# power_supply_module.net
KiCad netlist of a schematic drawn in EAGLE
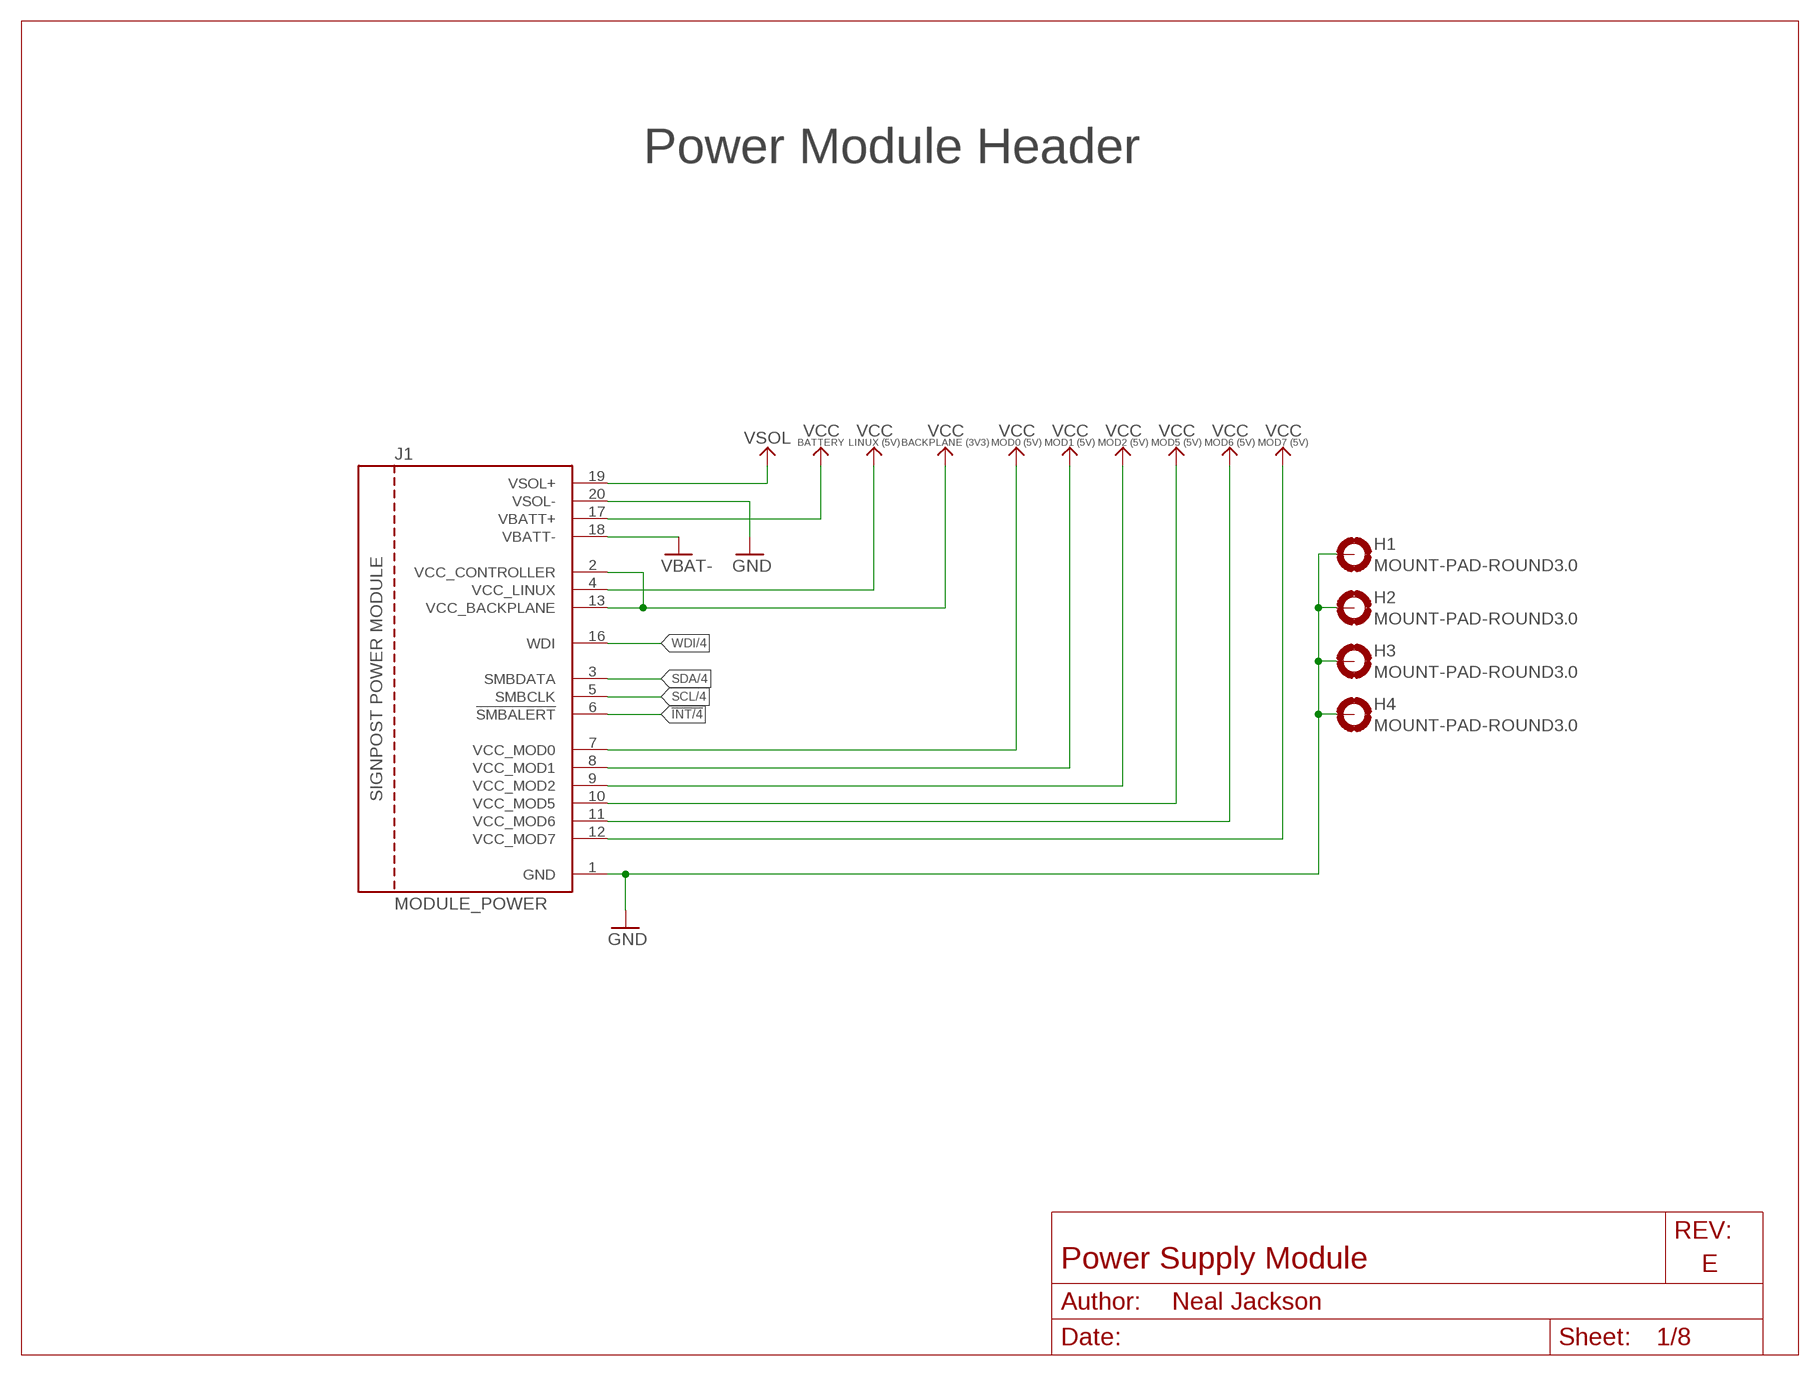
[diagram p0: schematic, sheet 1]
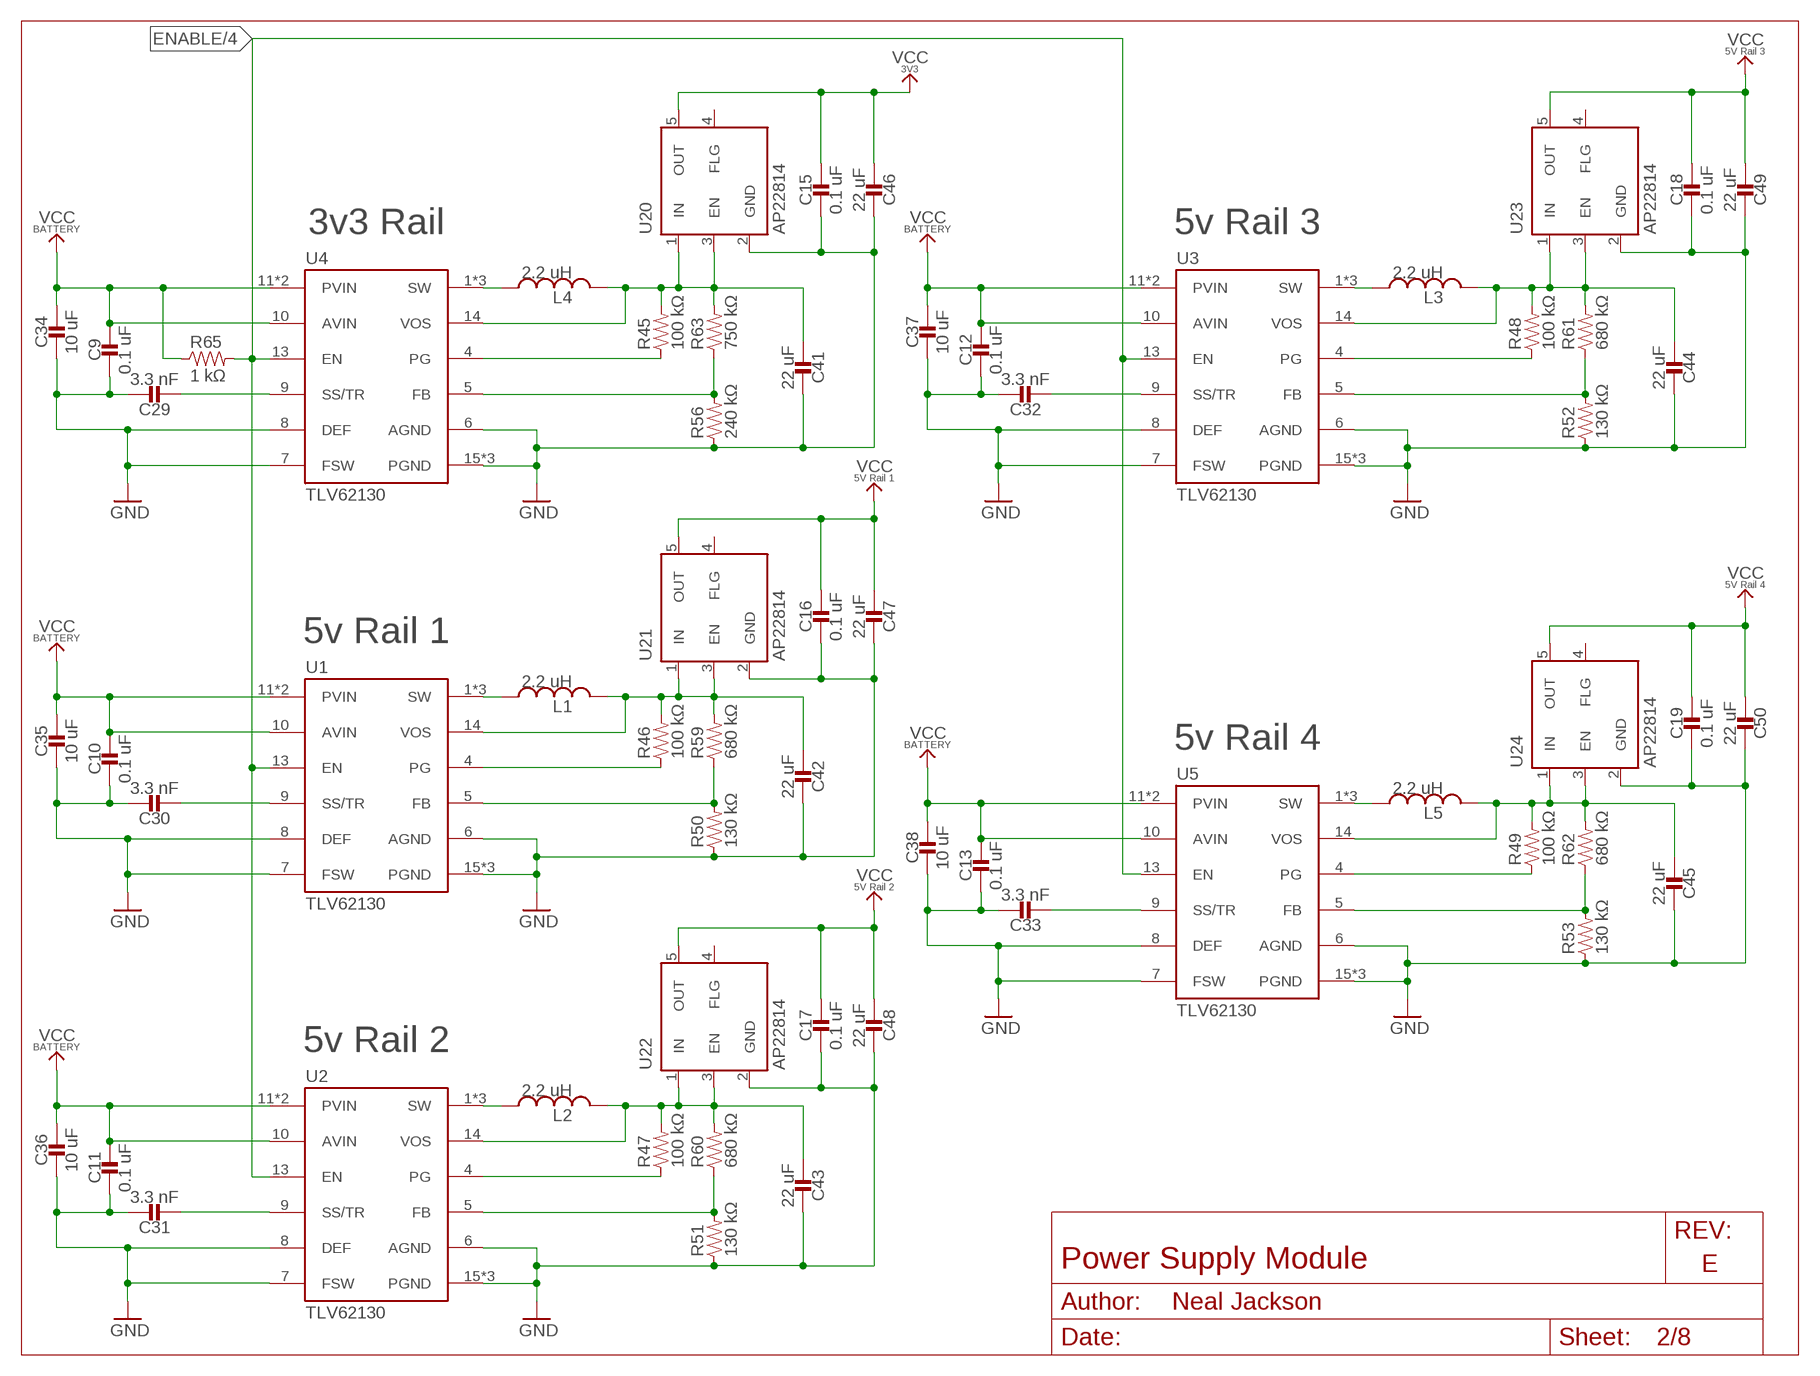
[diagram p1: schematic, sheet 2]
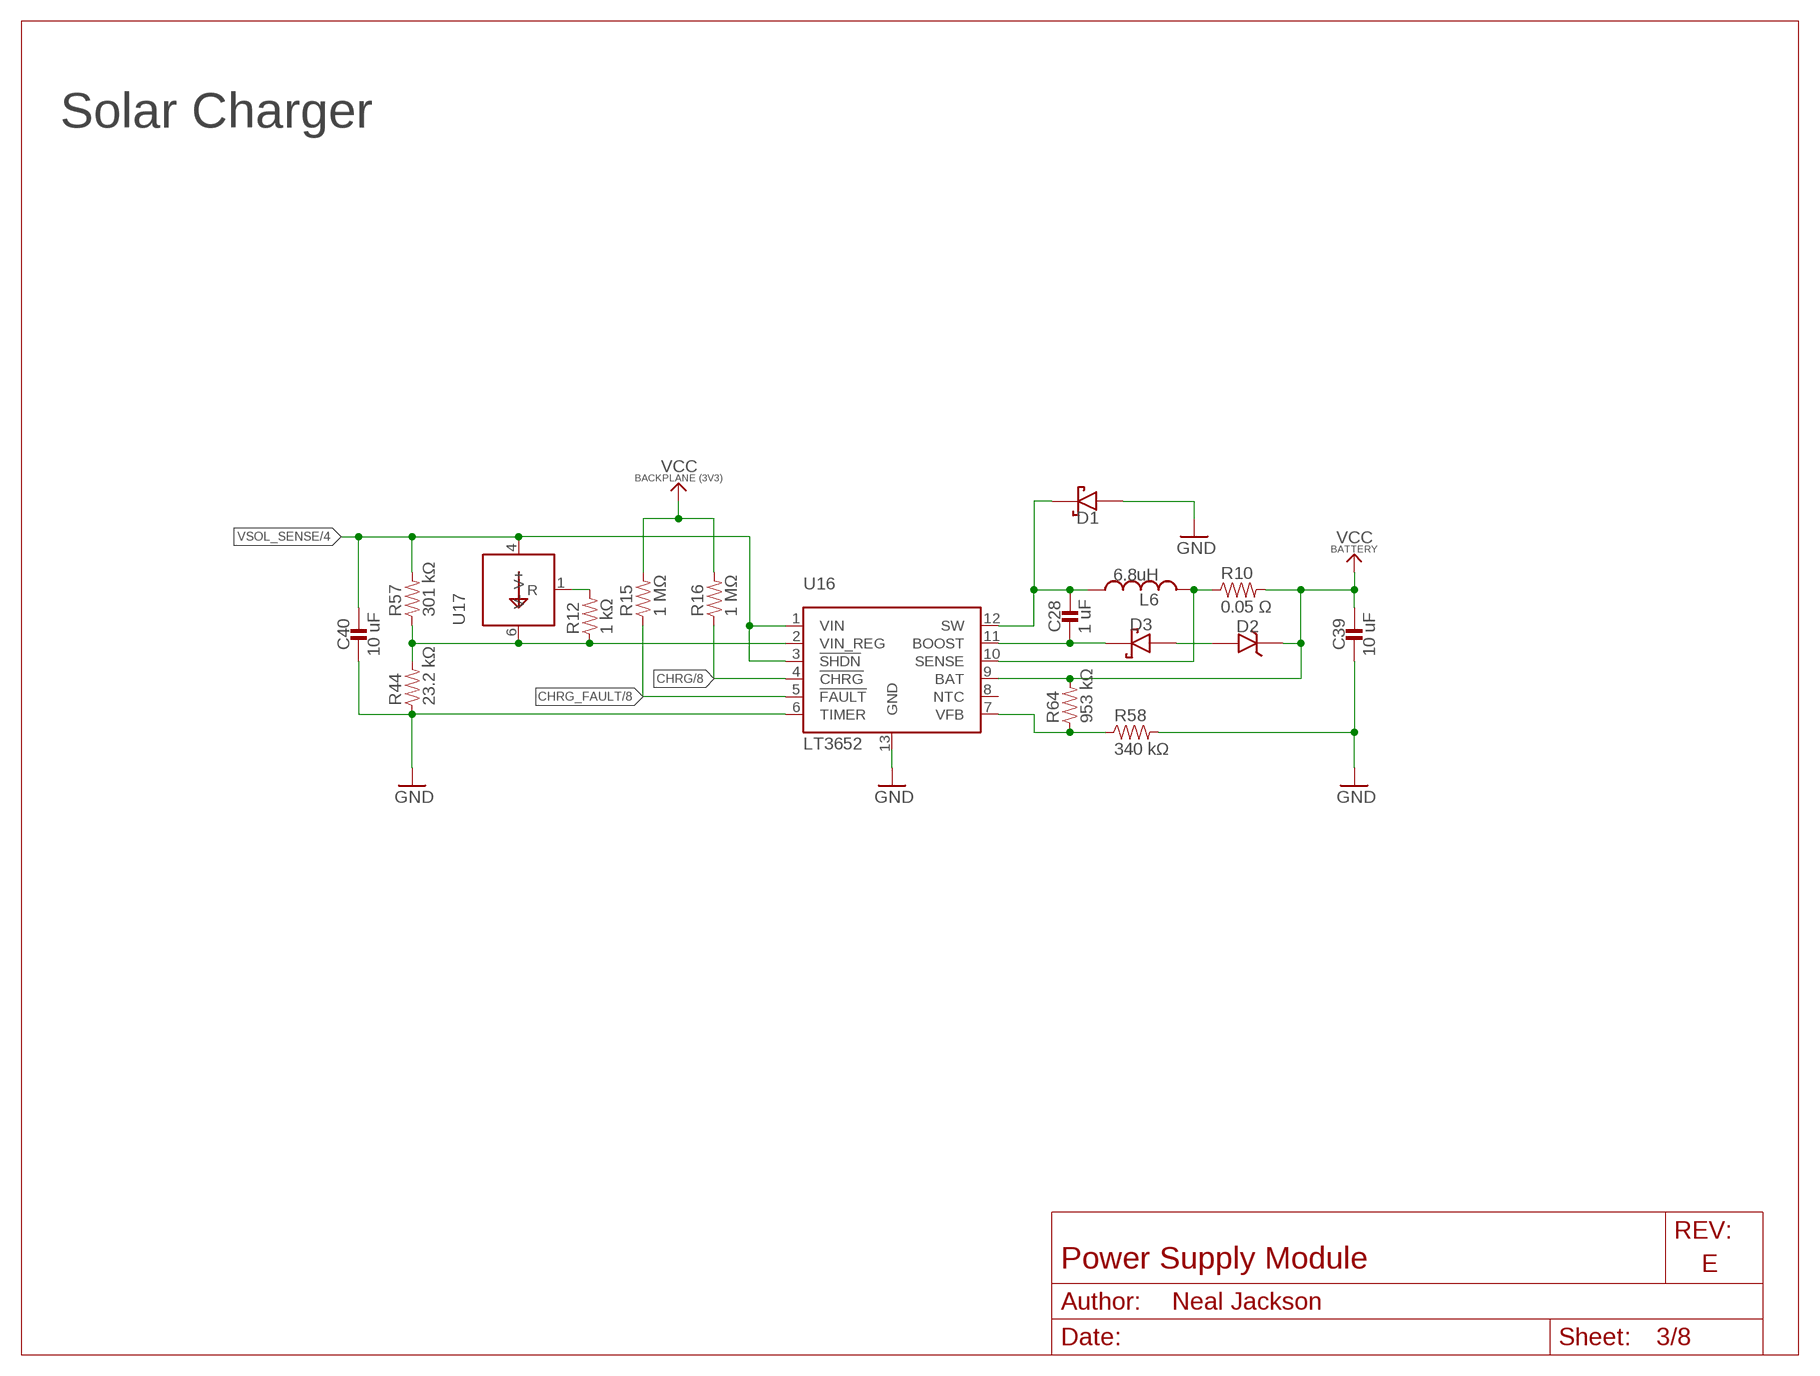
[diagram p2: schematic, sheet 3]
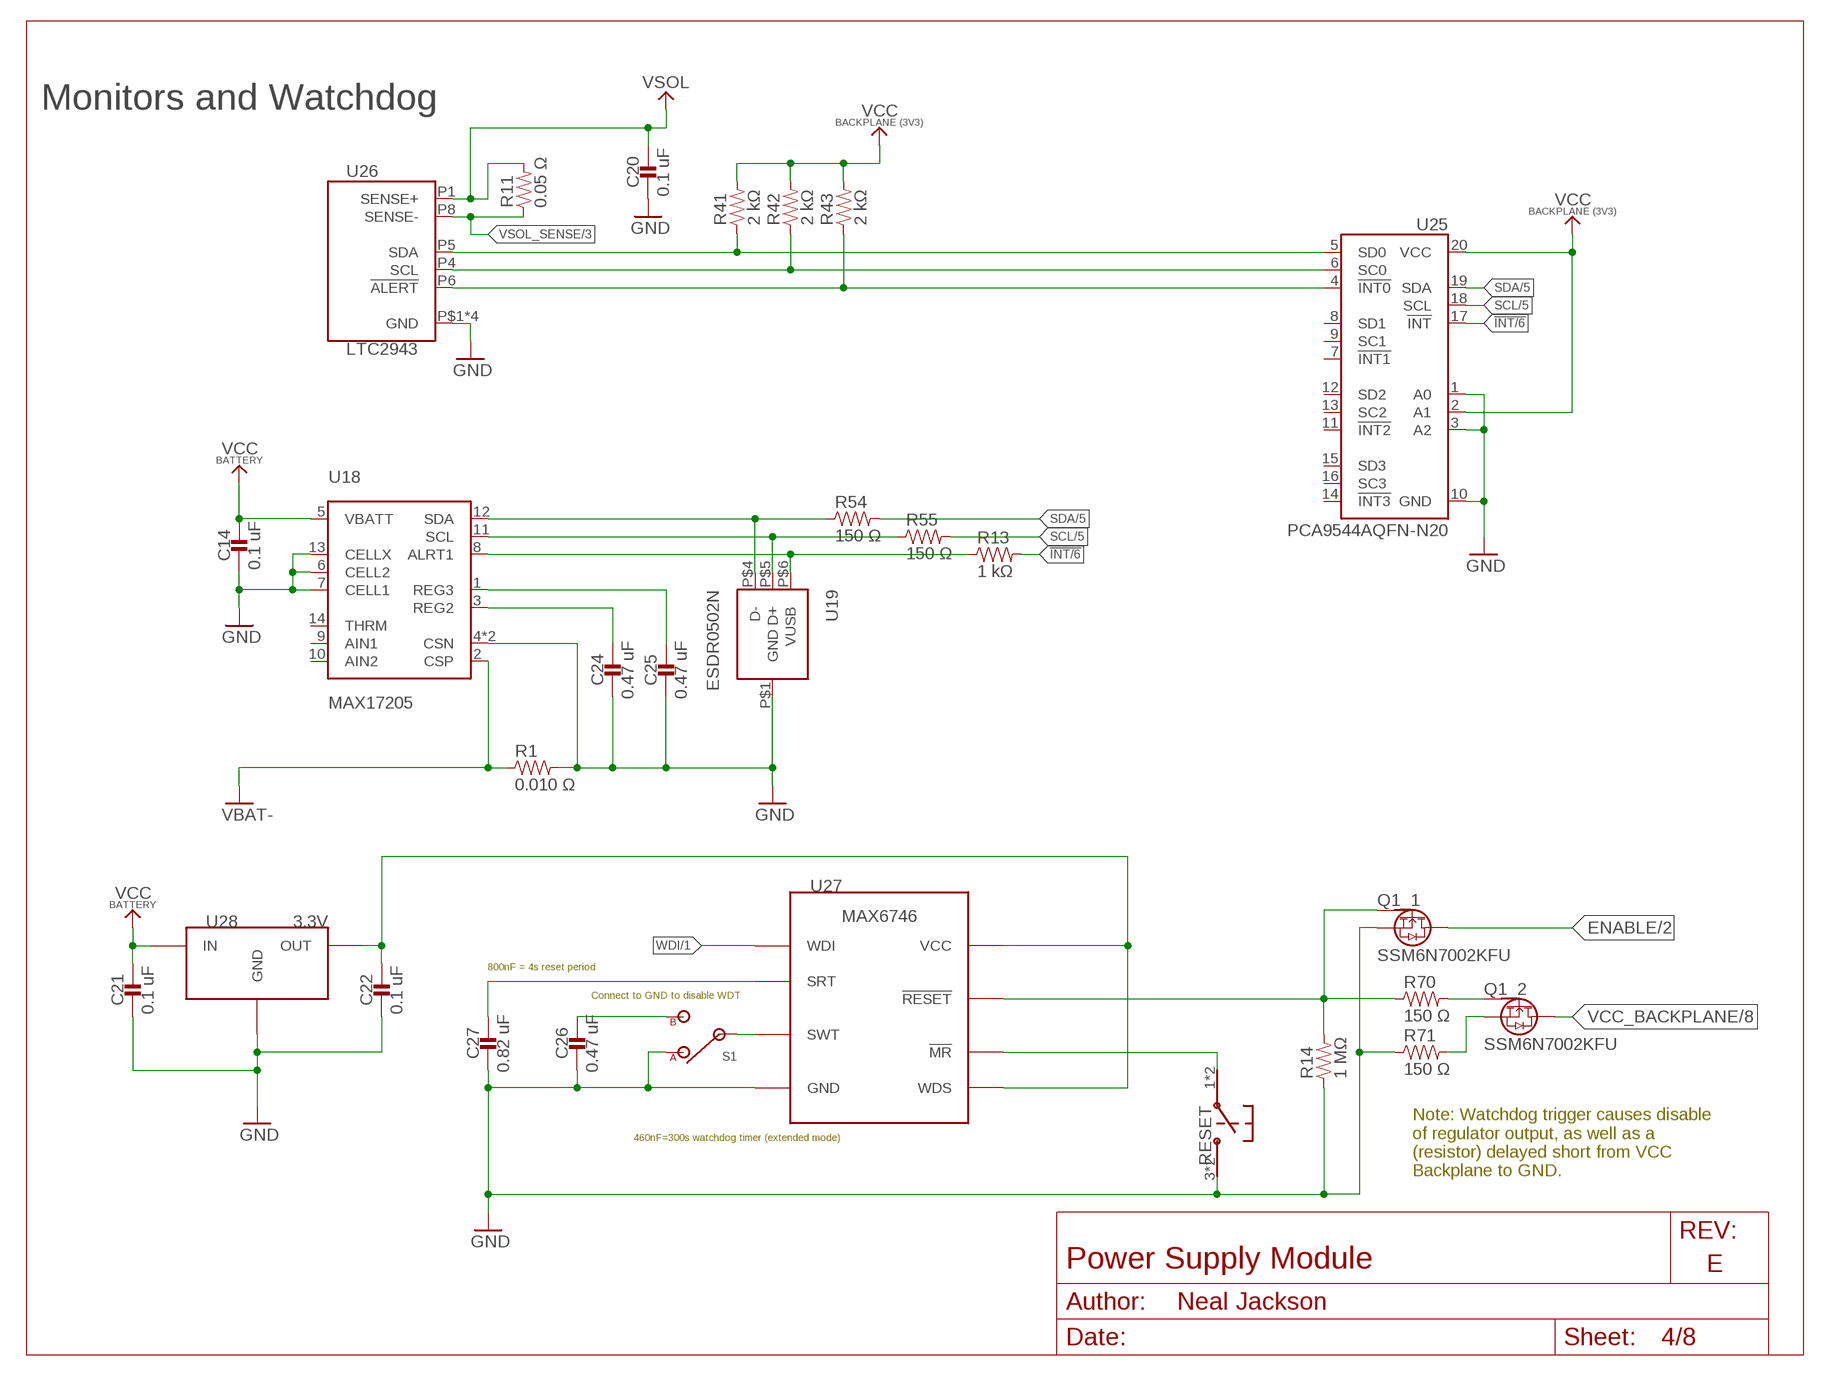
[diagram p3: schematic, sheet 4]
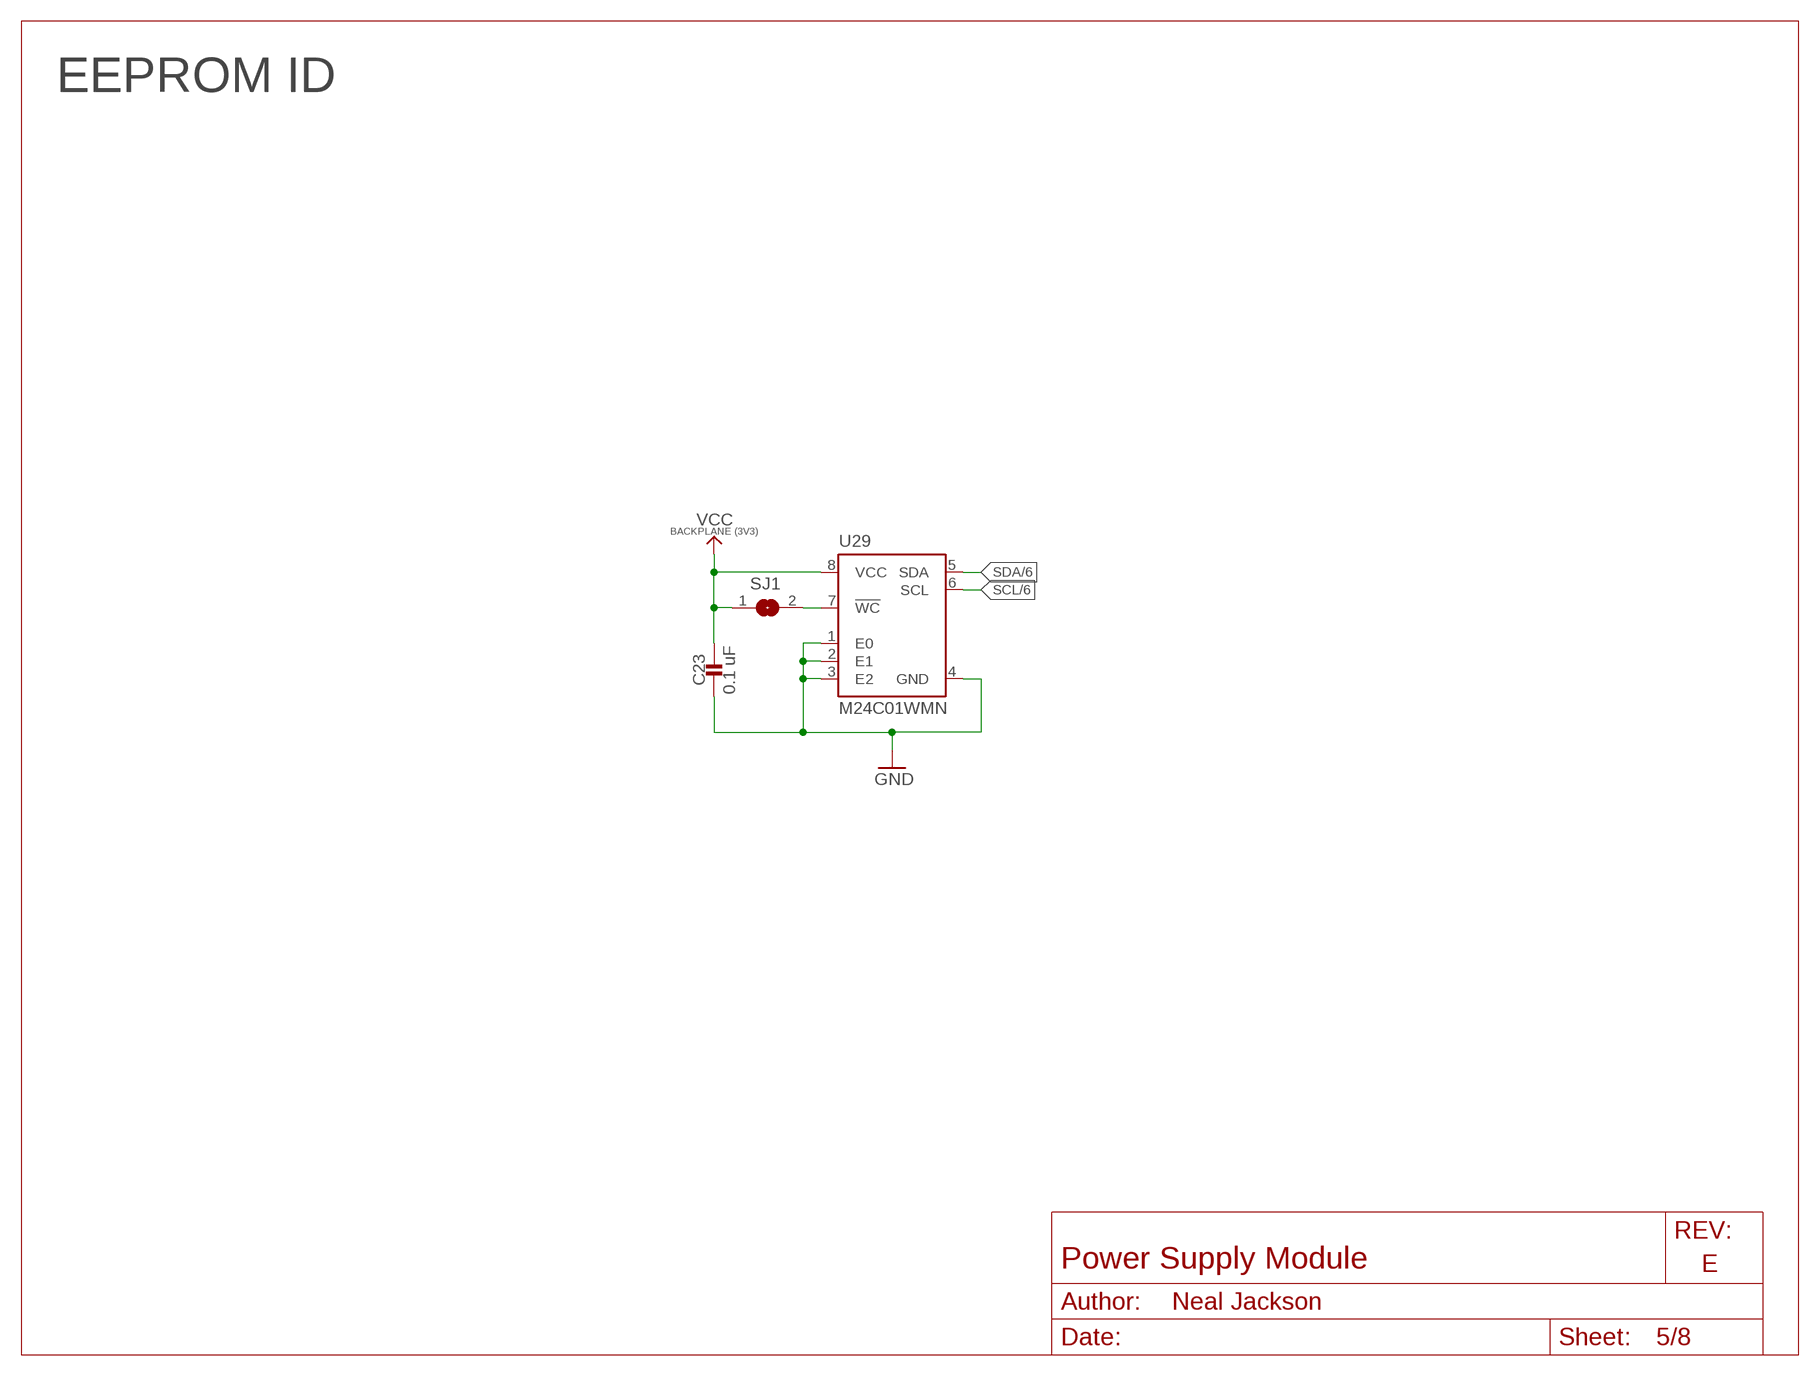
[diagram p4: schematic, sheet 5]
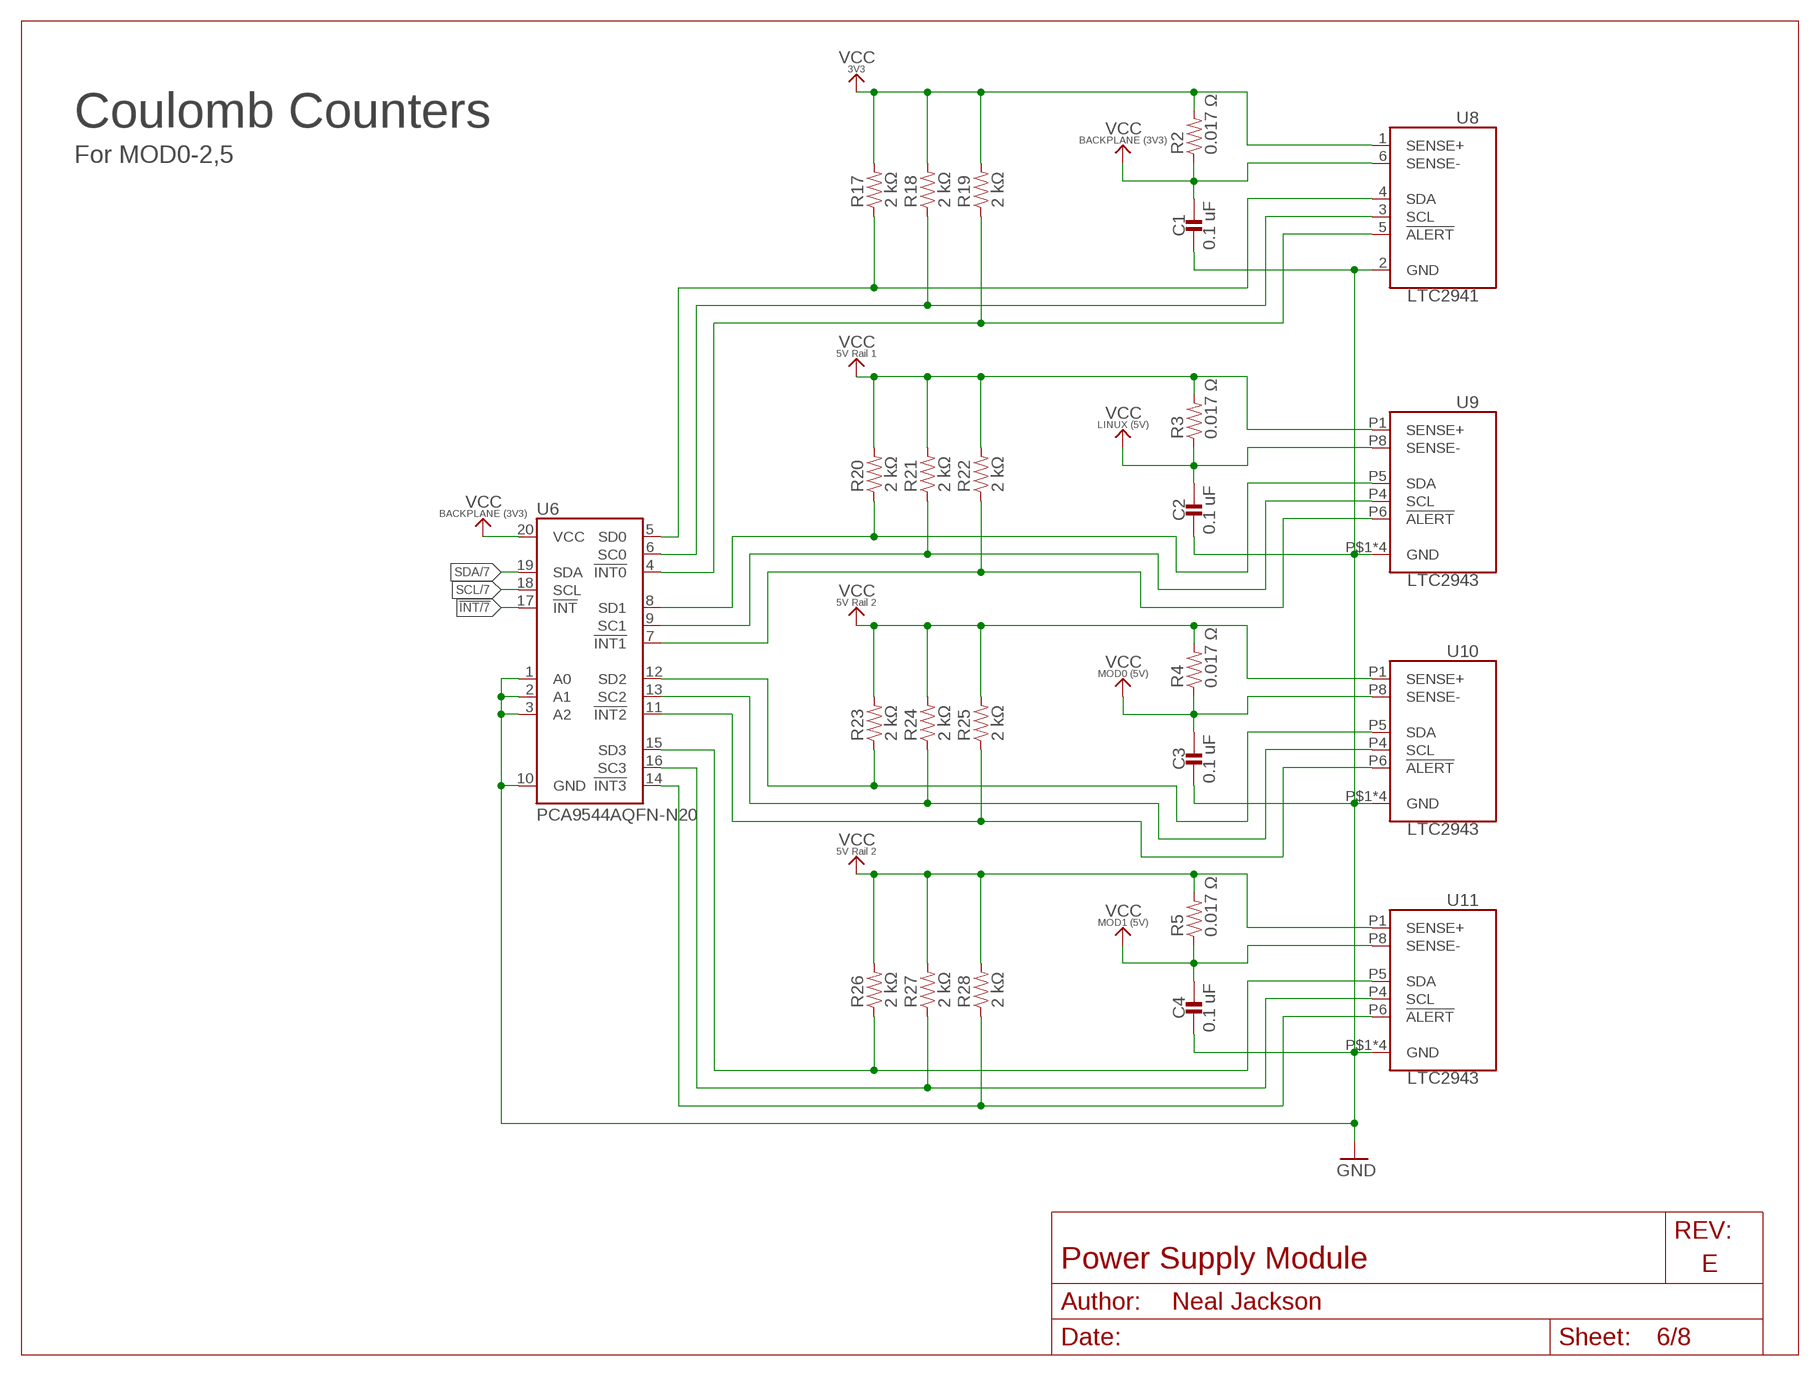
[diagram p5: schematic, sheet 6]
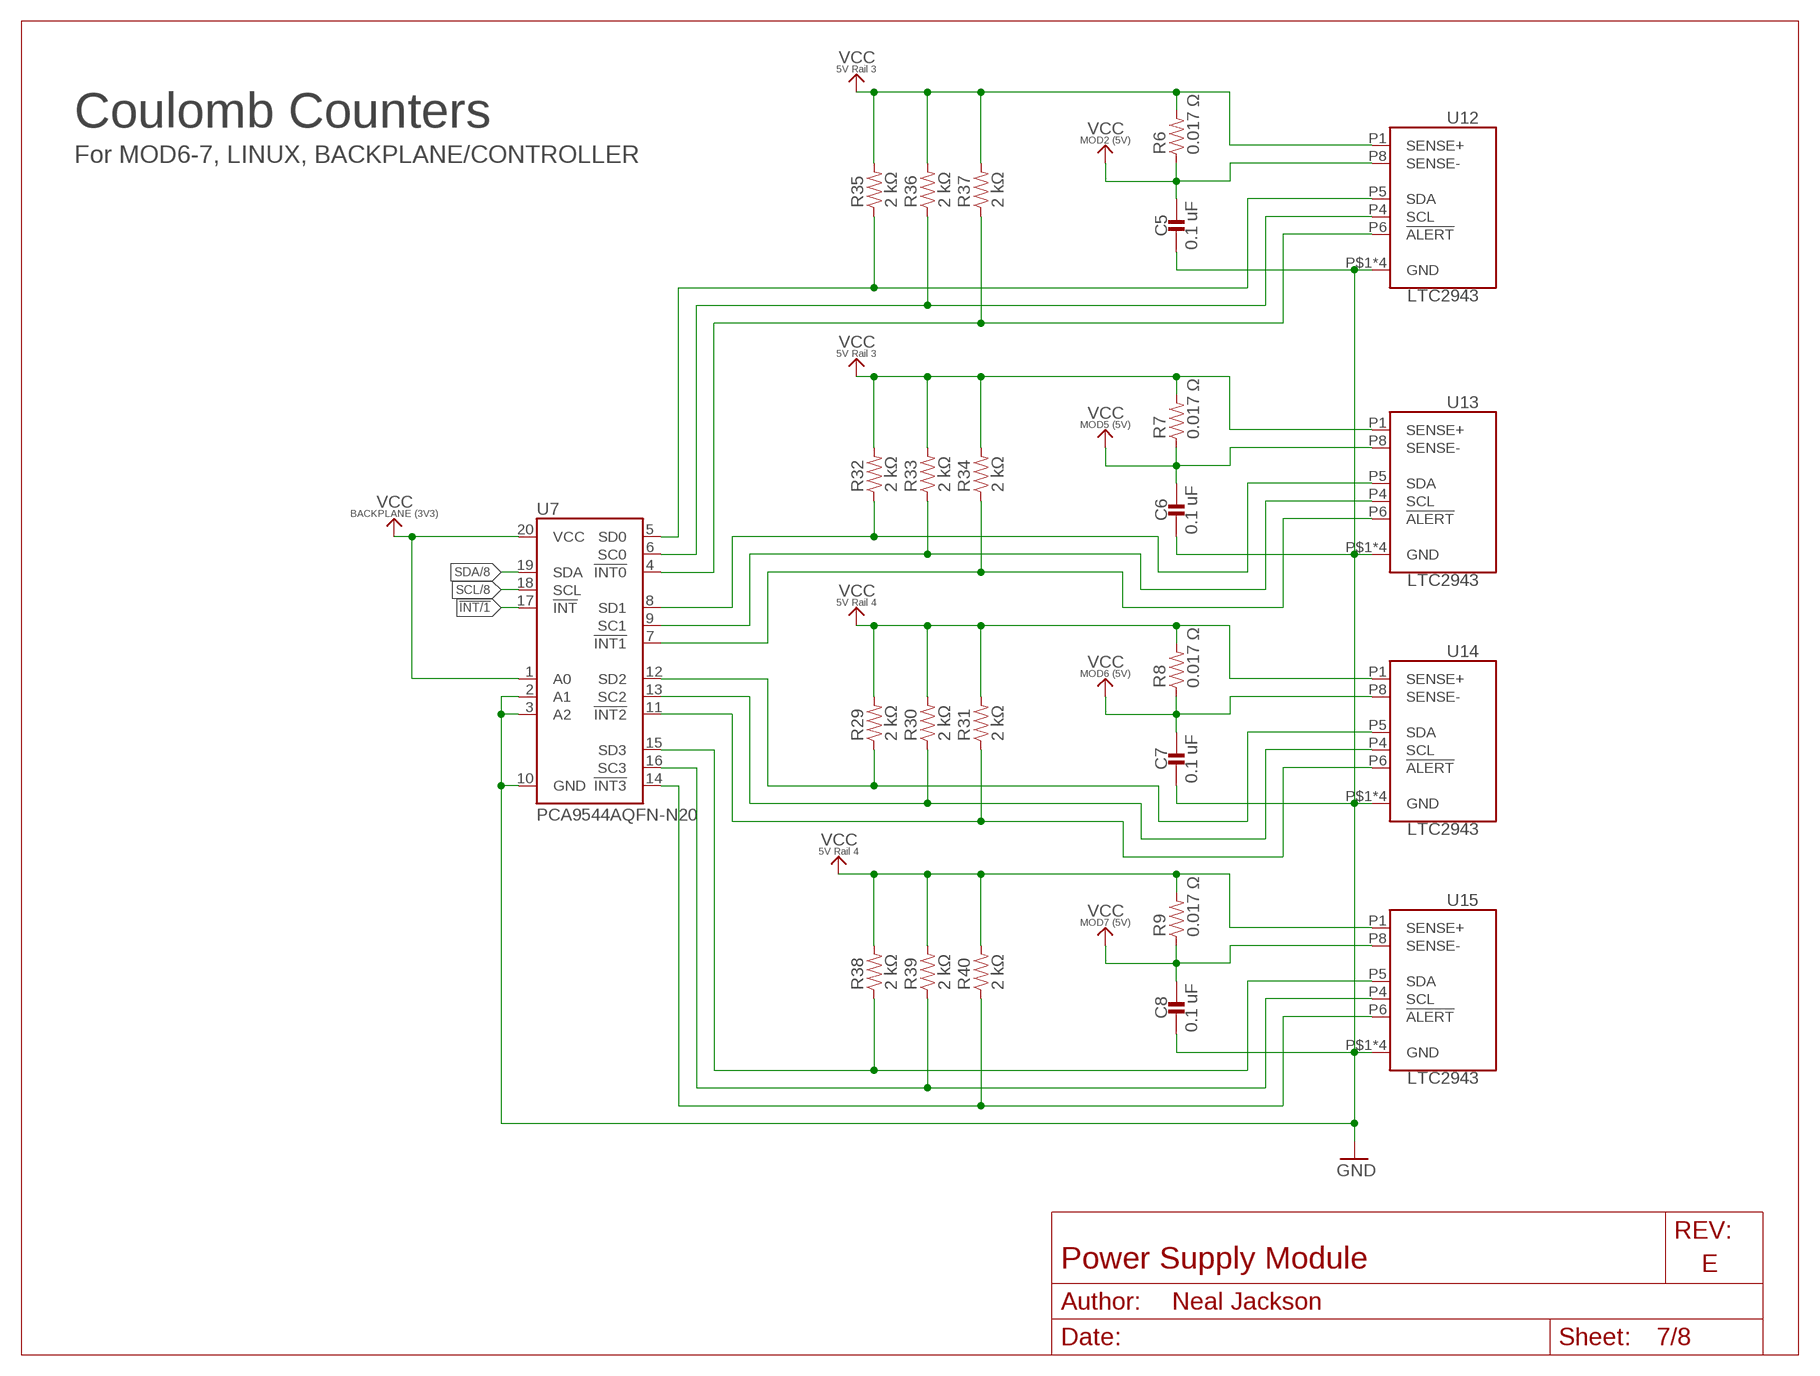
[diagram p6: schematic, sheet 7]
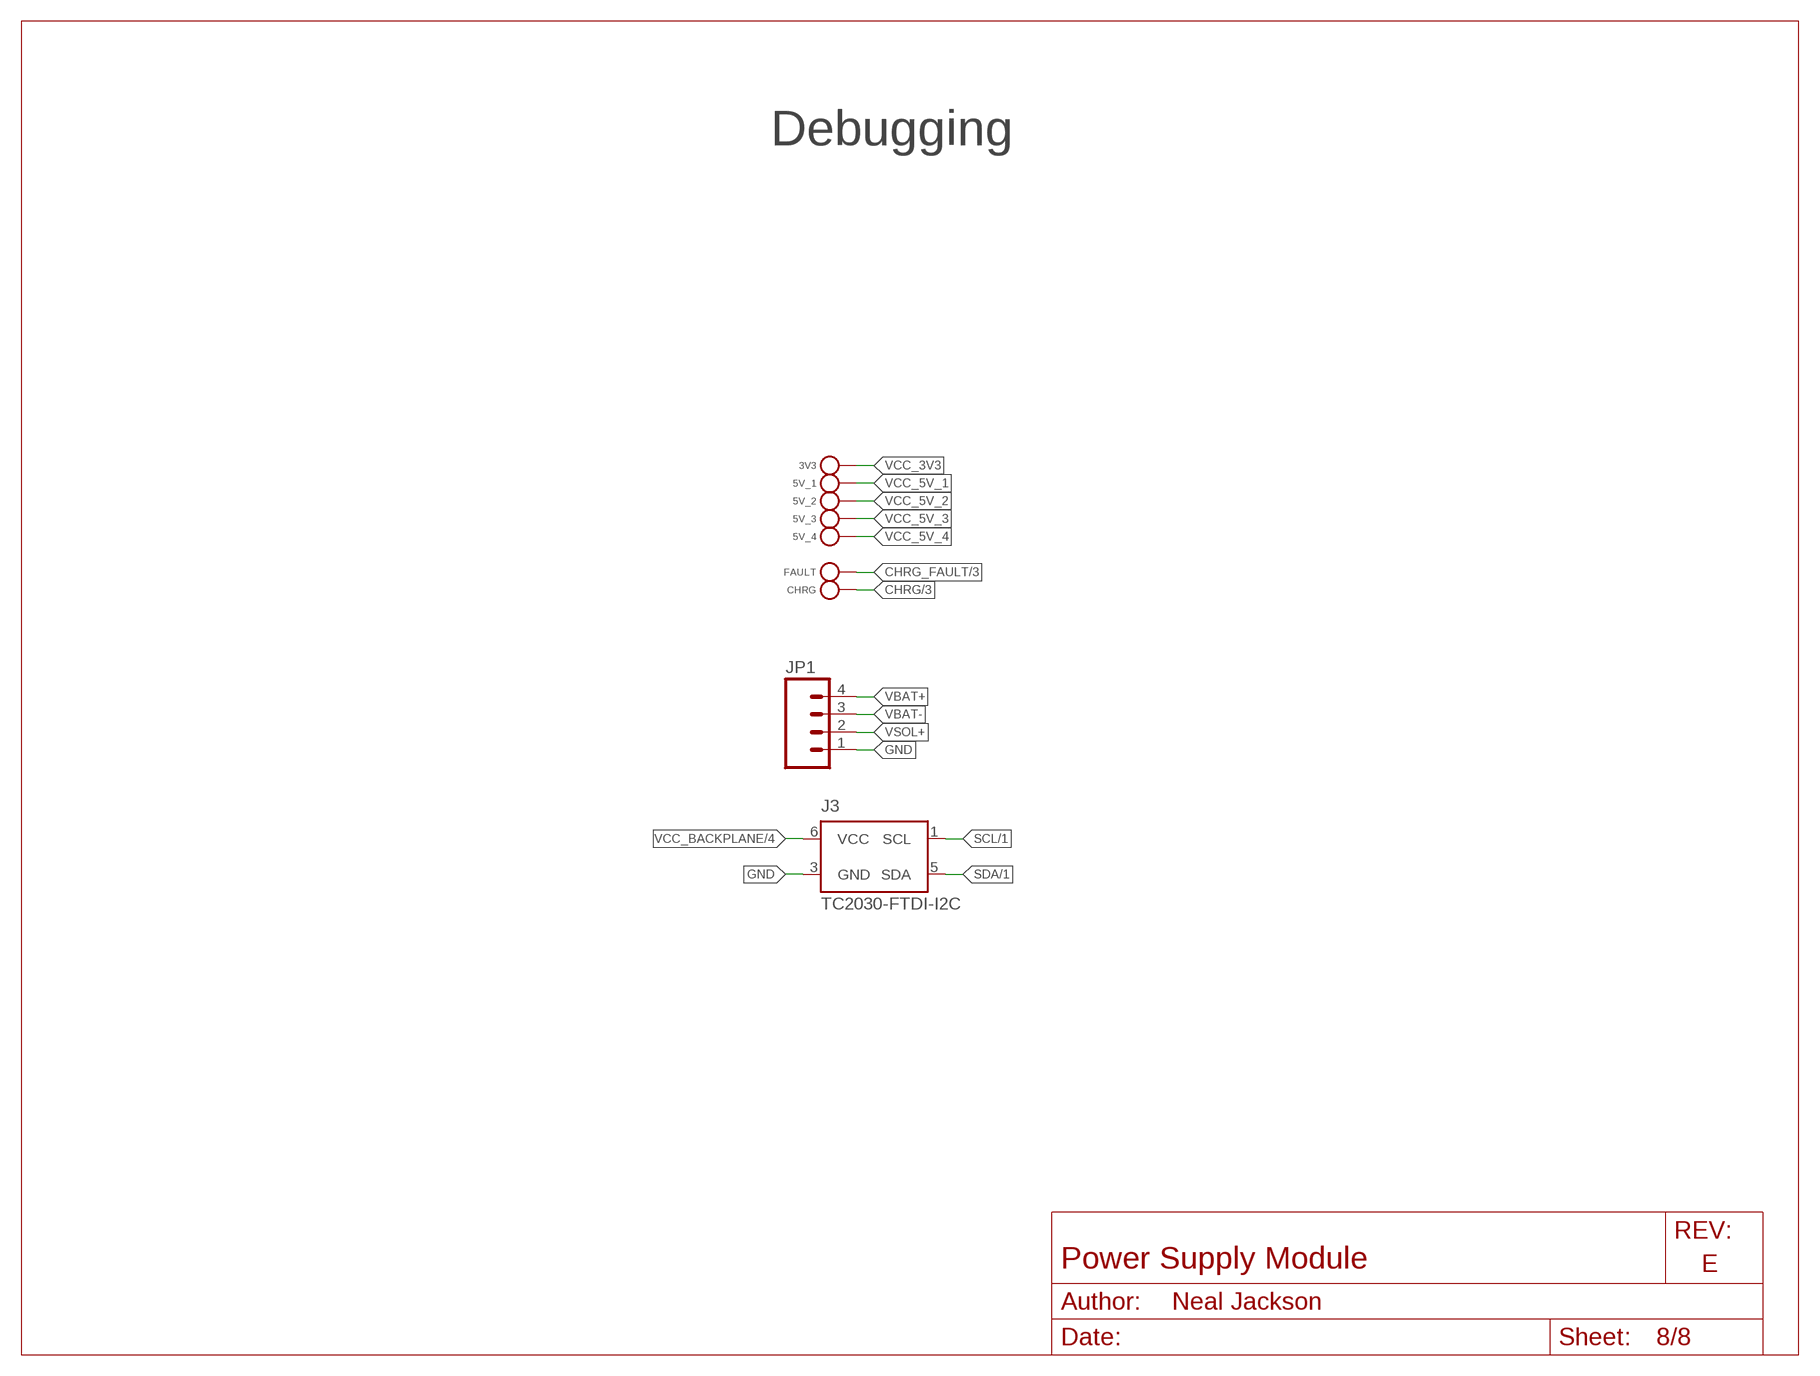
[diagram p7: schematic, sheet 8]

(export (version "E")
  (design (tool "Eeschema 10.0.6"))
  (components
    (comp (ref "C5")
      (value "0.1 uF")
      (footprint "eagle-import:0402_CAP")
      (libsource (lib "eagle-import") (part "CAPACITOR0402_CAP"))
    )
    (comp (ref "C6")
      (value "0.1 uF")
      (footprint "eagle-import:0402_CAP")
      (libsource (lib "eagle-import") (part "CAPACITOR0402_CAP"))
    )
    (comp (ref "C7")
      (value "0.1 uF")
      (footprint "eagle-import:0402_CAP")
      (libsource (lib "eagle-import") (part "CAPACITOR0402_CAP"))
    )
    (comp (ref "C8")
      (value "0.1 uF")
      (footprint "eagle-import:0402_CAP")
      (libsource (lib "eagle-import") (part "CAPACITOR0402_CAP"))
    )
    (comp (ref "R6")
      (value "0.017 Ω")
      (footprint "eagle-import:0805_RES")
      (libsource (lib "eagle-import") (part "RESISTOR0805_RES"))
    )
    (comp (ref "R7")
      (value "0.017 Ω")
      (footprint "eagle-import:0805_RES")
      (libsource (lib "eagle-import") (part "RESISTOR0805_RES"))
    )
    (comp (ref "R8")
      (value "0.017 Ω")
      (footprint "eagle-import:0805_RES")
      (libsource (lib "eagle-import") (part "RESISTOR0805_RES"))
    )
    (comp (ref "R9")
      (value "0.017 Ω")
      (footprint "eagle-import:0805_RES")
      (libsource (lib "eagle-import") (part "RESISTOR0805_RES"))
    )
    (comp (ref "R29")
      (value "2 kΩ")
      (footprint "eagle-import:0402_RES")
      (libsource (lib "eagle-import") (part "RESISTOR0402_RES"))
    )
    (comp (ref "R30")
      (value "2 kΩ")
      (footprint "eagle-import:0402_RES")
      (libsource (lib "eagle-import") (part "RESISTOR0402_RES"))
    )
    (comp (ref "R31")
      (value "2 kΩ")
      (footprint "eagle-import:0402_RES")
      (libsource (lib "eagle-import") (part "RESISTOR0402_RES"))
    )
    (comp (ref "R32")
      (value "2 kΩ")
      (footprint "eagle-import:0402_RES")
      (libsource (lib "eagle-import") (part "RESISTOR0402_RES"))
    )
    (comp (ref "R33")
      (value "2 kΩ")
      (footprint "eagle-import:0402_RES")
      (libsource (lib "eagle-import") (part "RESISTOR0402_RES"))
    )
    (comp (ref "R34")
      (value "2 kΩ")
      (footprint "eagle-import:0402_RES")
      (libsource (lib "eagle-import") (part "RESISTOR0402_RES"))
    )
    (comp (ref "R35")
      (value "2 kΩ")
      (footprint "eagle-import:0402_RES")
      (libsource (lib "eagle-import") (part "RESISTOR0402_RES"))
    )
    (comp (ref "R36")
      (value "2 kΩ")
      (footprint "eagle-import:0402_RES")
      (libsource (lib "eagle-import") (part "RESISTOR0402_RES"))
    )
    (comp (ref "R37")
      (value "2 kΩ")
      (footprint "eagle-import:0402_RES")
      (libsource (lib "eagle-import") (part "RESISTOR0402_RES"))
    )
    (comp (ref "R38")
      (value "2 kΩ")
      (footprint "eagle-import:0402_RES")
      (libsource (lib "eagle-import") (part "RESISTOR0402_RES"))
    )
    (comp (ref "R39")
      (value "2 kΩ")
      (footprint "eagle-import:0402_RES")
      (libsource (lib "eagle-import") (part "RESISTOR0402_RES"))
    )
    (comp (ref "R40")
      (value "2 kΩ")
      (footprint "eagle-import:0402_RES")
      (libsource (lib "eagle-import") (part "RESISTOR0402_RES"))
    )
    (comp (ref "U7")
      (value "PCA9544AQFN-N20")
      (footprint "eagle-import:QFN-N20")
      (libsource (lib "eagle-import") (part "PCA9544AQFN-N20"))
    )
    (comp (ref "U12")
      (value "LTC2943")
      (footprint "eagle-import:DFN-8")
      (libsource (lib "eagle-import") (part "LTC2943"))
    )
    (comp (ref "U13")
      (value "LTC2943")
      (footprint "eagle-import:DFN-8")
      (libsource (lib "eagle-import") (part "LTC2943"))
    )
    (comp (ref "U14")
      (value "LTC2943")
      (footprint "eagle-import:DFN-8")
      (libsource (lib "eagle-import") (part "LTC2943"))
    )
    (comp (ref "U15")
      (value "LTC2943")
      (footprint "eagle-import:DFN-8")
      (libsource (lib "eagle-import") (part "LTC2943"))
    )
    (comp (ref "C1")
      (value "0.1 uF")
      (footprint "eagle-import:0402_CAP")
      (libsource (lib "eagle-import") (part "CAPACITOR0402_CAP"))
    )
    (comp (ref "C2")
      (value "0.1 uF")
      (footprint "eagle-import:0402_CAP")
      (libsource (lib "eagle-import") (part "CAPACITOR0402_CAP"))
    )
    (comp (ref "C3")
      (value "0.1 uF")
      (footprint "eagle-import:0402_CAP")
      (libsource (lib "eagle-import") (part "CAPACITOR0402_CAP"))
    )
    (comp (ref "C4")
      (value "0.1 uF")
      (footprint "eagle-import:0402_CAP")
      (libsource (lib "eagle-import") (part "CAPACITOR0402_CAP"))
    )
    (comp (ref "R2")
      (value "0.017 Ω")
      (footprint "eagle-import:0805_RES")
      (libsource (lib "eagle-import") (part "RESISTOR0805_RES"))
    )
    (comp (ref "R3")
      (value "0.017 Ω")
      (footprint "eagle-import:0805_RES")
      (libsource (lib "eagle-import") (part "RESISTOR0805_RES"))
    )
    (comp (ref "R4")
      (value "0.017 Ω")
      (footprint "eagle-import:0805_RES")
      (libsource (lib "eagle-import") (part "RESISTOR0805_RES"))
    )
    (comp (ref "R5")
      (value "0.017 Ω")
      (footprint "eagle-import:0805_RES")
      (libsource (lib "eagle-import") (part "RESISTOR0805_RES"))
    )
    (comp (ref "R17")
      (value "2 kΩ")
      (footprint "eagle-import:0402_RES")
      (libsource (lib "eagle-import") (part "RESISTOR0402_RES"))
    )
    (comp (ref "R18")
      (value "2 kΩ")
      (footprint "eagle-import:0402_RES")
      (libsource (lib "eagle-import") (part "RESISTOR0402_RES"))
    )
    (comp (ref "R19")
      (value "2 kΩ")
      (footprint "eagle-import:0402_RES")
      (libsource (lib "eagle-import") (part "RESISTOR0402_RES"))
    )
    (comp (ref "R20")
      (value "2 kΩ")
      (footprint "eagle-import:0402_RES")
      (libsource (lib "eagle-import") (part "RESISTOR0402_RES"))
    )
    (comp (ref "R21")
      (value "2 kΩ")
      (footprint "eagle-import:0402_RES")
      (libsource (lib "eagle-import") (part "RESISTOR0402_RES"))
    )
    (comp (ref "R22")
      (value "2 kΩ")
      (footprint "eagle-import:0402_RES")
      (libsource (lib "eagle-import") (part "RESISTOR0402_RES"))
    )
    (comp (ref "R23")
      (value "2 kΩ")
      (footprint "eagle-import:0402_RES")
      (libsource (lib "eagle-import") (part "RESISTOR0402_RES"))
    )
    (comp (ref "R24")
      (value "2 kΩ")
      (footprint "eagle-import:0402_RES")
      (libsource (lib "eagle-import") (part "RESISTOR0402_RES"))
    )
    (comp (ref "R25")
      (value "2 kΩ")
      (footprint "eagle-import:0402_RES")
      (libsource (lib "eagle-import") (part "RESISTOR0402_RES"))
    )
    (comp (ref "R26")
      (value "2 kΩ")
      (footprint "eagle-import:0402_RES")
      (libsource (lib "eagle-import") (part "RESISTOR0402_RES"))
    )
    (comp (ref "R27")
      (value "2 kΩ")
      (footprint "eagle-import:0402_RES")
      (libsource (lib "eagle-import") (part "RESISTOR0402_RES"))
    )
    (comp (ref "R28")
      (value "2 kΩ")
      (footprint "eagle-import:0402_RES")
      (libsource (lib "eagle-import") (part "RESISTOR0402_RES"))
    )
    (comp (ref "U6")
      (value "PCA9544AQFN-N20")
      (footprint "eagle-import:QFN-N20")
      (libsource (lib "eagle-import") (part "PCA9544AQFN-N20"))
    )
    (comp (ref "U8")
      (value "LTC2941")
      (footprint "eagle-import:DFN-6-2MMX3MM")
      (libsource (lib "eagle-import") (part "LTC2941"))
    )
    (comp (ref "U9")
      (value "LTC2943")
      (footprint "eagle-import:DFN-8")
      (libsource (lib "eagle-import") (part "LTC2943"))
    )
    (comp (ref "U10")
      (value "LTC2943")
      (footprint "eagle-import:DFN-8")
      (libsource (lib "eagle-import") (part "LTC2943"))
    )
    (comp (ref "U11")
      (value "LTC2943")
      (footprint "eagle-import:DFN-8")
      (libsource (lib "eagle-import") (part "LTC2943"))
    )
    (comp (ref "C9")
      (value "0.1 uF")
      (footprint "eagle-import:0402_CAP")
      (libsource (lib "eagle-import") (part "CAPACITOR0402_CAP"))
    )
    (comp (ref "C10")
      (value "0.1 uF")
      (footprint "eagle-import:0402_CAP")
      (libsource (lib "eagle-import") (part "CAPACITOR0402_CAP"))
    )
    (comp (ref "C11")
      (value "0.1 uF")
      (footprint "eagle-import:0402_CAP")
      (libsource (lib "eagle-import") (part "CAPACITOR0402_CAP"))
    )
    (comp (ref "C12")
      (value "0.1 uF")
      (footprint "eagle-import:0402_CAP")
      (libsource (lib "eagle-import") (part "CAPACITOR0402_CAP"))
    )
    (comp (ref "C13")
      (value "0.1 uF")
      (footprint "eagle-import:0402_CAP")
      (libsource (lib "eagle-import") (part "CAPACITOR0402_CAP"))
    )
    (comp (ref "C15")
      (value "0.1 uF")
      (footprint "eagle-import:0402_CAP")
      (libsource (lib "eagle-import") (part "CAPACITOR0402_CAP"))
    )
    (comp (ref "C16")
      (value "0.1 uF")
      (footprint "eagle-import:0402_CAP")
      (libsource (lib "eagle-import") (part "CAPACITOR0402_CAP"))
    )
    (comp (ref "C17")
      (value "0.1 uF")
      (footprint "eagle-import:0402_CAP")
      (libsource (lib "eagle-import") (part "CAPACITOR0402_CAP"))
    )
    (comp (ref "C18")
      (value "0.1 uF")
      (footprint "eagle-import:0402_CAP")
      (libsource (lib "eagle-import") (part "CAPACITOR0402_CAP"))
    )
    (comp (ref "C19")
      (value "0.1 uF")
      (footprint "eagle-import:0402_CAP")
      (libsource (lib "eagle-import") (part "CAPACITOR0402_CAP"))
    )
    (comp (ref "C29")
      (value "3.3 nF")
      (footprint "eagle-import:0402_CAP")
      (libsource (lib "eagle-import") (part "CAPACITOR0402_CAP"))
    )
    (comp (ref "C30")
      (value "3.3 nF")
      (footprint "eagle-import:0402_CAP")
      (libsource (lib "eagle-import") (part "CAPACITOR0402_CAP"))
    )
    (comp (ref "C31")
      (value "3.3 nF")
      (footprint "eagle-import:0402_CAP")
      (libsource (lib "eagle-import") (part "CAPACITOR0402_CAP"))
    )
    (comp (ref "C32")
      (value "3.3 nF")
      (footprint "eagle-import:0402_CAP")
      (libsource (lib "eagle-import") (part "CAPACITOR0402_CAP"))
    )
    (comp (ref "C33")
      (value "3.3 nF")
      (footprint "eagle-import:0402_CAP")
      (libsource (lib "eagle-import") (part "CAPACITOR0402_CAP"))
    )
    (comp (ref "C34")
      (value "10 uF")
      (footprint "eagle-import:0805_CAP")
      (libsource (lib "eagle-import") (part "CAPACITOR0805_CAP"))
    )
    (comp (ref "C35")
      (value "10 uF")
      (footprint "eagle-import:0805_CAP")
      (libsource (lib "eagle-import") (part "CAPACITOR0805_CAP"))
    )
    (comp (ref "C36")
      (value "10 uF")
      (footprint "eagle-import:0805_CAP")
      (libsource (lib "eagle-import") (part "CAPACITOR0805_CAP"))
    )
    (comp (ref "C37")
      (value "10 uF")
      (footprint "eagle-import:0805_CAP")
      (libsource (lib "eagle-import") (part "CAPACITOR0805_CAP"))
    )
    (comp (ref "C38")
      (value "10 uF")
      (footprint "eagle-import:0805_CAP")
      (libsource (lib "eagle-import") (part "CAPACITOR0805_CAP"))
    )
    (comp (ref "C41")
      (value "22 uF")
      (footprint "eagle-import:0603_CAP")
      (libsource (lib "eagle-import") (part "CAPACITOR0603_CAP"))
    )
    (comp (ref "C42")
      (value "22 uF")
      (footprint "eagle-import:0603_CAP")
      (libsource (lib "eagle-import") (part "CAPACITOR0603_CAP"))
    )
    (comp (ref "C43")
      (value "22 uF")
      (footprint "eagle-import:0603_CAP")
      (libsource (lib "eagle-import") (part "CAPACITOR0603_CAP"))
    )
    (comp (ref "C44")
      (value "22 uF")
      (footprint "eagle-import:0603_CAP")
      (libsource (lib "eagle-import") (part "CAPACITOR0603_CAP"))
    )
    (comp (ref "C45")
      (value "22 uF")
      (footprint "eagle-import:0603_CAP")
      (libsource (lib "eagle-import") (part "CAPACITOR0603_CAP"))
    )
    (comp (ref "C46")
      (value "22 uF")
      (footprint "eagle-import:0603_CAP")
      (libsource (lib "eagle-import") (part "CAPACITOR0603_CAP"))
    )
    (comp (ref "C47")
      (value "22 uF")
      (footprint "eagle-import:0603_CAP")
      (libsource (lib "eagle-import") (part "CAPACITOR0603_CAP"))
    )
    (comp (ref "C48")
      (value "22 uF")
      (footprint "eagle-import:0603_CAP")
      (libsource (lib "eagle-import") (part "CAPACITOR0603_CAP"))
    )
    (comp (ref "C49")
      (value "22 uF")
      (footprint "eagle-import:0603_CAP")
      (libsource (lib "eagle-import") (part "CAPACITOR0603_CAP"))
    )
    (comp (ref "C50")
      (value "22 uF")
      (footprint "eagle-import:0603_CAP")
      (libsource (lib "eagle-import") (part "CAPACITOR0603_CAP"))
    )
    (comp (ref "L1")
      (value "2.2 uH")
      (footprint "eagle-import:IHL-1212BZ-11")
      (fields (field (name "MF") "Vishay Dale"))
      (libsource (lib "eagle-import") (part "INDUCTORIHL"))
    )
    (comp (ref "L2")
      (value "2.2 uH")
      (footprint "eagle-import:IHL-1212BZ-11")
      (fields (field (name "MF") "Vishay Dale"))
      (libsource (lib "eagle-import") (part "INDUCTORIHL"))
    )
    (comp (ref "L3")
      (value "2.2 uH")
      (footprint "eagle-import:IHL-1212BZ-11")
      (fields (field (name "MF") "Vishay Dale"))
      (libsource (lib "eagle-import") (part "INDUCTORIHL"))
    )
    (comp (ref "L4")
      (value "2.2 uH")
      (footprint "eagle-import:IHL-1212BZ-11")
      (fields (field (name "MF") "Vishay Dale"))
      (libsource (lib "eagle-import") (part "INDUCTORIHL"))
    )
    (comp (ref "L5")
      (value "2.2 uH")
      (footprint "eagle-import:IHL-1212BZ-11")
      (fields (field (name "MF") "Vishay Dale"))
      (libsource (lib "eagle-import") (part "INDUCTORIHL"))
    )
    (comp (ref "R45")
      (value "100 kΩ")
      (footprint "eagle-import:0402_RES")
      (libsource (lib "eagle-import") (part "RESISTOR0402_RES"))
    )
    (comp (ref "R46")
      (value "100 kΩ")
      (footprint "eagle-import:0402_RES")
      (libsource (lib "eagle-import") (part "RESISTOR0402_RES"))
    )
    (comp (ref "R47")
      (value "100 kΩ")
      (footprint "eagle-import:0402_RES")
      (libsource (lib "eagle-import") (part "RESISTOR0402_RES"))
    )
    (comp (ref "R48")
      (value "100 kΩ")
      (footprint "eagle-import:0402_RES")
      (libsource (lib "eagle-import") (part "RESISTOR0402_RES"))
    )
    (comp (ref "R49")
      (value "100 kΩ")
      (footprint "eagle-import:0402_RES")
      (libsource (lib "eagle-import") (part "RESISTOR0402_RES"))
    )
    (comp (ref "R50")
      (value "130 kΩ")
      (footprint "eagle-import:0402_RES")
      (libsource (lib "eagle-import") (part "RESISTOR0402_RES"))
    )
    (comp (ref "R51")
      (value "130 kΩ")
      (footprint "eagle-import:0402_RES")
      (libsource (lib "eagle-import") (part "RESISTOR0402_RES"))
    )
    (comp (ref "R52")
      (value "130 kΩ")
      (footprint "eagle-import:0402_RES")
      (libsource (lib "eagle-import") (part "RESISTOR0402_RES"))
    )
    (comp (ref "R53")
      (value "130 kΩ")
      (footprint "eagle-import:0402_RES")
      (libsource (lib "eagle-import") (part "RESISTOR0402_RES"))
    )
    (comp (ref "R56")
      (value "240 kΩ")
      (footprint "eagle-import:0402_RES")
      (libsource (lib "eagle-import") (part "RESISTOR0402_RES"))
    )
    (comp (ref "R59")
      (value "680 kΩ")
      (footprint "eagle-import:0402_RES")
      (libsource (lib "eagle-import") (part "RESISTOR0402_RES"))
    )
    (comp (ref "R60")
      (value "680 kΩ")
      (footprint "eagle-import:0402_RES")
      (libsource (lib "eagle-import") (part "RESISTOR0402_RES"))
    )
    (comp (ref "R61")
      (value "680 kΩ")
      (footprint "eagle-import:0402_RES")
      (libsource (lib "eagle-import") (part "RESISTOR0402_RES"))
    )
    (comp (ref "R62")
      (value "680 kΩ")
      (footprint "eagle-import:0402_RES")
      (libsource (lib "eagle-import") (part "RESISTOR0402_RES"))
    )
    (comp (ref "R63")
      (value "750 kΩ")
      (footprint "eagle-import:0402_RES")
      (libsource (lib "eagle-import") (part "RESISTOR0402_RES"))
    )
    (comp (ref "R65")
      (value "1 kΩ")
      (footprint "eagle-import:0402_RES")
      (libsource (lib "eagle-import") (part "RESISTOR0402_RES"))
    )
    (comp (ref "U1")
      (value "TLV62130")
      (footprint "eagle-import:TQFN-16_3MM")
      (fields (field (name "MF") "Texas Instruments"))
      (libsource (lib "eagle-import") (part "TLV62130"))
    )
    (comp (ref "U2")
      (value "TLV62130")
      (footprint "eagle-import:TQFN-16_3MM")
      (fields (field (name "MF") "Texas Instruments"))
      (libsource (lib "eagle-import") (part "TLV62130"))
    )
    (comp (ref "U3")
      (value "TLV62130")
      (footprint "eagle-import:TQFN-16_3MM")
      (fields (field (name "MF") "Texas Instruments"))
      (libsource (lib "eagle-import") (part "TLV62130"))
    )
    (comp (ref "U4")
      (value "TLV62130")
      (footprint "eagle-import:TQFN-16_3MM")
      (fields (field (name "MF") "Texas Instruments"))
      (libsource (lib "eagle-import") (part "TLV62130"))
    )
    (comp (ref "U5")
      (value "TLV62130")
      (footprint "eagle-import:TQFN-16_3MM")
      (fields (field (name "MF") "Texas Instruments"))
      (libsource (lib "eagle-import") (part "TLV62130"))
    )
    (comp (ref "U20")
      (value "AP22814")
      (footprint "eagle-import:U-DFN2020-6")
      (libsource (lib "eagle-import") (part "AP22814"))
    )
    (comp (ref "U21")
      (value "AP22814")
      (footprint "eagle-import:U-DFN2020-6")
      (libsource (lib "eagle-import") (part "AP22814"))
    )
    (comp (ref "U22")
      (value "AP22814")
      (footprint "eagle-import:U-DFN2020-6")
      (libsource (lib "eagle-import") (part "AP22814"))
    )
    (comp (ref "U23")
      (value "AP22814")
      (footprint "eagle-import:U-DFN2020-6")
      (libsource (lib "eagle-import") (part "AP22814"))
    )
    (comp (ref "U24")
      (value "AP22814")
      (footprint "eagle-import:U-DFN2020-6")
      (libsource (lib "eagle-import") (part "AP22814"))
    )
    (comp (ref "3V3")
      (value "TEST_POINT_0.040IN")
      (footprint "eagle-import:TESTPOINT_0.040IN")
      (libsource (lib "eagle-import") (part "TEST_POINT_0.040IN"))
    )
    (comp (ref "5V_1")
      (value "TEST_POINT_0.040IN")
      (footprint "eagle-import:TESTPOINT_0.040IN")
      (libsource (lib "eagle-import") (part "TEST_POINT_0.040IN"))
    )
    (comp (ref "5V_2")
      (value "TEST_POINT_0.040IN")
      (footprint "eagle-import:TESTPOINT_0.040IN")
      (libsource (lib "eagle-import") (part "TEST_POINT_0.040IN"))
    )
    (comp (ref "5V_3")
      (value "TEST_POINT_0.040IN")
      (footprint "eagle-import:TESTPOINT_0.040IN")
      (libsource (lib "eagle-import") (part "TEST_POINT_0.040IN"))
    )
    (comp (ref "5V_4")
      (value "TEST_POINT_0.040IN")
      (footprint "eagle-import:TESTPOINT_0.040IN")
      (libsource (lib "eagle-import") (part "TEST_POINT_0.040IN"))
    )
    (comp (ref "CHRG")
      (value "TEST_POINT_0.040IN")
      (footprint "eagle-import:TESTPOINT_0.040IN")
      (libsource (lib "eagle-import") (part "TEST_POINT_0.040IN"))
    )
    (comp (ref "FAULT")
      (value "TEST_POINT_0.040IN")
      (footprint "eagle-import:TESTPOINT_0.040IN")
      (libsource (lib "eagle-import") (part "TEST_POINT_0.040IN"))
    )
    (comp (ref "J3")
      (value "TC2030-FTDI-I2C")
      (footprint "eagle-import:TC2030-IDC-NL")
      (libsource (lib "eagle-import") (part "TC2030-FTDI-I2C"))
    )
    (comp (ref "JP1")
      (value "M04PTH")
      (footprint "eagle-import:1X04")
      (libsource (lib "eagle-import") (part "M04PTH"))
    )
    (comp (ref "H1")
      (value "MOUNT-PAD-ROUND3.0")
      (footprint "eagle-import:3,0-PAD")
      (libsource (lib "eagle-import") (part "MOUNT-PAD-ROUND3.0"))
    )
    (comp (ref "H2")
      (value "MOUNT-PAD-ROUND3.0")
      (footprint "eagle-import:3,0-PAD")
      (libsource (lib "eagle-import") (part "MOUNT-PAD-ROUND3.0"))
    )
    (comp (ref "H3")
      (value "MOUNT-PAD-ROUND3.0")
      (footprint "eagle-import:3,0-PAD")
      (libsource (lib "eagle-import") (part "MOUNT-PAD-ROUND3.0"))
    )
    (comp (ref "H4")
      (value "MOUNT-PAD-ROUND3.0")
      (footprint "eagle-import:3,0-PAD")
      (libsource (lib "eagle-import") (part "MOUNT-PAD-ROUND3.0"))
    )
    (comp (ref "J1")
      (value "MODULE_POWER")
      (footprint "eagle-import:MODULE_POWER")
      (libsource (lib "eagle-import") (part "MODULE_POWER"))
    )
    (comp (ref "C28")
      (value "1 uF")
      (footprint "eagle-import:0603_CAP")
      (libsource (lib "eagle-import") (part "CAPACITOR0603_CAP"))
    )
    (comp (ref "C39")
      (value "10 uF")
      (footprint "eagle-import:0805_CAP")
      (libsource (lib "eagle-import") (part "CAPACITOR0805_CAP"))
    )
    (comp (ref "C40")
      (value "10 uF")
      (footprint "eagle-import:0805_CAP")
      (libsource (lib "eagle-import") (part "CAPACITOR0805_CAP"))
    )
    (comp (ref "D1")
      (value "DIODE_SCHOTTKYSOT-23F")
      (footprint "eagle-import:SOT-23F")
      (libsource (lib "eagle-import") (part "DIODE_SCHOTTKYSOT-23F"))
    )
    (comp (ref "D2")
      (value "DIODE_ZENERSOT323")
      (footprint "eagle-import:SOD323")
      (libsource (lib "eagle-import") (part "DIODE_ZENERSOT323"))
    )
    (comp (ref "D3")
      (value "DIODE_SCHOTTKYSOD323")
      (footprint "eagle-import:SOD323")
      (libsource (lib "eagle-import") (part "DIODE_SCHOTTKYSOD323"))
    )
    (comp (ref "L6")
      (value "6.8uH")
      (footprint "eagle-import:IHL-2525CZ")
      (libsource (lib "eagle-import") (part "INDUCTORIHL2525CZ"))
    )
    (comp (ref "R10")
      (value "0.05 Ω")
      (footprint "eagle-import:0805_RES")
      (libsource (lib "eagle-import") (part "RESISTOR0805_RES"))
    )
    (comp (ref "R12")
      (value "1 kΩ")
      (footprint "eagle-import:0402_RES")
      (libsource (lib "eagle-import") (part "RESISTOR0402_RES"))
    )
    (comp (ref "R15")
      (value "1 MΩ")
      (footprint "eagle-import:0402_RES")
      (libsource (lib "eagle-import") (part "RESISTOR0402_RES"))
    )
    (comp (ref "R16")
      (value "1 MΩ")
      (footprint "eagle-import:0402_RES")
      (libsource (lib "eagle-import") (part "RESISTOR0402_RES"))
    )
    (comp (ref "R44")
      (value "23.2 kΩ")
      (footprint "eagle-import:0805_RES")
      (libsource (lib "eagle-import") (part "RESISTOR0805_RES"))
    )
    (comp (ref "R57")
      (value "301 kΩ")
      (footprint "eagle-import:0805_RES")
      (libsource (lib "eagle-import") (part "RESISTOR0805_RES"))
    )
    (comp (ref "R58")
      (value "340 kΩ")
      (footprint "eagle-import:0805_RES")
      (libsource (lib "eagle-import") (part "RESISTOR0805_RES"))
    )
    (comp (ref "R64")
      (value "953 kΩ")
      (footprint "eagle-import:0805_RES")
      (libsource (lib "eagle-import") (part "RESISTOR0805_RES"))
    )
    (comp (ref "U16")
      (value "LT3652")
      (footprint "eagle-import:DFN-12_3MM")
      (libsource (lib "eagle-import") (part "LT3652"))
    )
    (comp (ref "U17")
      (value "LM234")
      (footprint "eagle-import:SOIC-8")
      (libsource (lib "eagle-import") (part "LM234"))
    )
    (comp (ref "C14")
      (value "0.1 uF")
      (footprint "eagle-import:0402_CAP")
      (libsource (lib "eagle-import") (part "CAPACITOR0402_CAP"))
    )
    (comp (ref "C20")
      (value "0.1 uF")
      (footprint "eagle-import:0402_CAP")
      (libsource (lib "eagle-import") (part "CAPACITOR0402_CAP"))
    )
    (comp (ref "C21")
      (value "0.1 uF")
      (footprint "eagle-import:0402_CAP")
      (libsource (lib "eagle-import") (part "CAPACITOR0402_CAP"))
    )
    (comp (ref "C22")
      (value "0.1 uF")
      (footprint "eagle-import:0402_CAP")
      (libsource (lib "eagle-import") (part "CAPACITOR0402_CAP"))
    )
    (comp (ref "C24")
      (value "0.47 uF")
      (footprint "eagle-import:0402_CAP")
      (libsource (lib "eagle-import") (part "CAPACITOR0402_CAP"))
    )
    (comp (ref "C25")
      (value "0.47 uF")
      (footprint "eagle-import:0402_CAP")
      (libsource (lib "eagle-import") (part "CAPACITOR0402_CAP"))
    )
    (comp (ref "C26")
      (value "0.47 uF")
      (footprint "eagle-import:0402_CAP")
      (libsource (lib "eagle-import") (part "CAPACITOR0402_CAP"))
    )
    (comp (ref "C27")
      (value "0.82 uF")
      (footprint "eagle-import:0402_CAP")
      (libsource (lib "eagle-import") (part "CAPACITOR0402_CAP"))
    )
    (comp (ref "Q1")
      (value "SSM6N7002KFU")
      (footprint "eagle-import:1-2T1S")
      (libsource (lib "eagle-import") (part "SSM6N7002KFU"))
    )
    (comp (ref "R1")
      (value "0.010 Ω")
      (footprint "eagle-import:0805_RES")
      (libsource (lib "eagle-import") (part "RESISTOR0805_RES"))
    )
    (comp (ref "R11")
      (value "0.05 Ω")
      (footprint "eagle-import:0805_RES")
      (libsource (lib "eagle-import") (part "RESISTOR0805_RES"))
    )
    (comp (ref "R13")
      (value "1 kΩ")
      (footprint "eagle-import:0402_RES")
      (libsource (lib "eagle-import") (part "RESISTOR0402_RES"))
    )
    (comp (ref "R14")
      (value "1 MΩ")
      (footprint "eagle-import:0402_RES")
      (libsource (lib "eagle-import") (part "RESISTOR0402_RES"))
    )
    (comp (ref "R41")
      (value "2 kΩ")
      (footprint "eagle-import:0402_RES")
      (libsource (lib "eagle-import") (part "RESISTOR0402_RES"))
    )
    (comp (ref "R42")
      (value "2 kΩ")
      (footprint "eagle-import:0402_RES")
      (libsource (lib "eagle-import") (part "RESISTOR0402_RES"))
    )
    (comp (ref "R43")
      (value "2 kΩ")
      (footprint "eagle-import:0402_RES")
      (libsource (lib "eagle-import") (part "RESISTOR0402_RES"))
    )
    (comp (ref "R54")
      (value "150 Ω")
      (footprint "eagle-import:0402_RES")
      (libsource (lib "eagle-import") (part "RESISTOR0402_RES"))
    )
    (comp (ref "R55")
      (value "150 Ω")
      (footprint "eagle-import:0402_RES")
      (libsource (lib "eagle-import") (part "RESISTOR0402_RES"))
    )
    (comp (ref "R70")
      (value "150 Ω")
      (footprint "eagle-import:0402_RES")
      (libsource (lib "eagle-import") (part "RESISTOR0402_RES"))
    )
    (comp (ref "R71")
      (value "150 Ω")
      (footprint "eagle-import:0402_RES")
      (libsource (lib "eagle-import") (part "RESISTOR0402_RES"))
    )
    (comp (ref "RESET")
      (value "PTS810SJ")
      (footprint "eagle-import:PTS810SJ")
      (libsource (lib "eagle-import") (part "PTS810SJ"))
    )
    (comp (ref "S1")
      (value "TE_SSA12/SPDT")
      (footprint "eagle-import:TE_SSA12_SPDT")
      (libsource (lib "eagle-import") (part "TE_SSA12/SPDT"))
    )
    (comp (ref "U18")
      (value "MAX17205")
      (footprint "eagle-import:14-TDFN")
      (libsource (lib "eagle-import") (part "MAX17205"))
    )
    (comp (ref "U19")
      (value "ESDR0502N")
      (footprint "eagle-import:UDFN-6")
      (libsource (lib "eagle-import") (part "ESDR0502N"))
    )
    (comp (ref "U25")
      (value "PCA9544AQFN-N20")
      (footprint "eagle-import:QFN-N20")
      (libsource (lib "eagle-import") (part "PCA9544AQFN-N20"))
    )
    (comp (ref "U26")
      (value "LTC2943")
      (footprint "eagle-import:DFN-8")
      (libsource (lib "eagle-import") (part "LTC2943"))
    )
    (comp (ref "U27")
      (value "MAX6746")
      (footprint "eagle-import:SOT-23-8")
      (libsource (lib "eagle-import") (part "MAX6746"))
    )
    (comp (ref "U28")
      (value "3.3V")
      (footprint "eagle-import:SOT-23")
      (fields (field (name "DIGIKEY") "ZMR330FCT-ND"))
      (libsource (lib "eagle-import") (part "TILM34803.3V"))
    )
    (comp (ref "C23")
      (value "0.1 uF")
      (footprint "eagle-import:0402_CAP")
      (libsource (lib "eagle-import") (part "CAPACITOR0402_CAP"))
    )
    (comp (ref "SJ1") (value "SJ") (footprint "eagle-import:SJ") (libsource (lib "eagle-import") (part "SJ")))
    (comp (ref "U29")
      (value "M24C01WMN")
      (footprint "eagle-import:SOIC-8")
      (libsource (lib "eagle-import") (part "M24C01WMN"))
    )
  )
  (nets
    (net (code "1") (name "CHRG") (class "Default")
      (node (ref "CHRG") (pin "TESTPOINT") (pinfunction "TESTPOINT_TESTPOINT") (pintype "bidirectional"))
      (node (ref "R16") (pin "1") (pinfunction "1_1") (pintype "passive"))
      (node (ref "U16") (pin "4") (pinfunction "~{CHRG}_4") (pintype "bidirectional"))
    )
    (net (code "2") (name "CHRG_FAULT") (class "Default")
      (node (ref "FAULT") (pin "TESTPOINT") (pinfunction "TESTPOINT_TESTPOINT") (pintype "bidirectional"))
      (node (ref "R15") (pin "1") (pinfunction "1_1") (pintype "passive"))
      (node (ref "U16") (pin "5") (pinfunction "~{FAULT}_5") (pintype "bidirectional"))
    )
    (net (code "3") (name "ENABLE") (class "Default")
      (node (ref "Q1") (pin "6") (pinfunction "D_6") (pintype "bidirectional"))
      (node (ref "R65") (pin "2") (pinfunction "2_2") (pintype "passive"))
      (node (ref "U1") (pin "13") (pinfunction "EN_13") (pintype "bidirectional"))
      (node (ref "U2") (pin "13") (pinfunction "EN_13") (pintype "bidirectional"))
      (node (ref "U3") (pin "13") (pinfunction "EN_13") (pintype "bidirectional"))
      (node (ref "U4") (pin "13") (pinfunction "EN_13") (pintype "bidirectional"))
      (node (ref "U5") (pin "13") (pinfunction "EN_13") (pintype "bidirectional"))
    )
    (net (code "4") (name "GND") (class "Default")
      (node (ref "C1") (pin "2") (pinfunction "2_2") (pintype "bidirectional"))
      (node (ref "C10") (pin "2") (pinfunction "2_2") (pintype "bidirectional"))
      (node (ref "C11") (pin "2") (pinfunction "2_2") (pintype "bidirectional"))
      (node (ref "C12") (pin "2") (pinfunction "2_2") (pintype "bidirectional"))
      (node (ref "C13") (pin "2") (pinfunction "2_2") (pintype "bidirectional"))
      (node (ref "C14") (pin "2") (pinfunction "2_2") (pintype "bidirectional"))
      (node (ref "C15") (pin "2") (pinfunction "2_2") (pintype "bidirectional"))
      (node (ref "C16") (pin "2") (pinfunction "2_2") (pintype "bidirectional"))
      (node (ref "C17") (pin "2") (pinfunction "2_2") (pintype "bidirectional"))
      (node (ref "C18") (pin "2") (pinfunction "2_2") (pintype "bidirectional"))
      (node (ref "C19") (pin "2") (pinfunction "2_2") (pintype "bidirectional"))
      (node (ref "C2") (pin "2") (pinfunction "2_2") (pintype "bidirectional"))
      (node (ref "C20") (pin "2") (pinfunction "2_2") (pintype "bidirectional"))
      (node (ref "C21") (pin "2") (pinfunction "2_2") (pintype "bidirectional"))
      (node (ref "C22") (pin "2") (pinfunction "2_2") (pintype "bidirectional"))
      (node (ref "C23") (pin "2") (pinfunction "2_2") (pintype "bidirectional"))
      (node (ref "C24") (pin "2") (pinfunction "2_2") (pintype "bidirectional"))
      (node (ref "C25") (pin "2") (pinfunction "2_2") (pintype "bidirectional"))
      (node (ref "C26") (pin "2") (pinfunction "2_2") (pintype "bidirectional"))
      (node (ref "C27") (pin "2") (pinfunction "2_2") (pintype "bidirectional"))
      (node (ref "C29") (pin "1") (pinfunction "1_1") (pintype "bidirectional"))
      (node (ref "C3") (pin "2") (pinfunction "2_2") (pintype "bidirectional"))
      (node (ref "C30") (pin "1") (pinfunction "1_1") (pintype "bidirectional"))
      (node (ref "C31") (pin "1") (pinfunction "1_1") (pintype "bidirectional"))
      (node (ref "C32") (pin "1") (pinfunction "1_1") (pintype "bidirectional"))
      (node (ref "C33") (pin "1") (pinfunction "1_1") (pintype "bidirectional"))
      (node (ref "C34") (pin "P$2") (pinfunction "2_P$2") (pintype "bidirectional"))
      (node (ref "C35") (pin "P$2") (pinfunction "2_P$2") (pintype "bidirectional"))
      (node (ref "C36") (pin "P$2") (pinfunction "2_P$2") (pintype "bidirectional"))
      (node (ref "C37") (pin "P$2") (pinfunction "2_P$2") (pintype "bidirectional"))
      (node (ref "C38") (pin "P$2") (pinfunction "2_P$2") (pintype "bidirectional"))
      (node (ref "C39") (pin "P$2") (pinfunction "2_P$2") (pintype "bidirectional"))
      (node (ref "C4") (pin "2") (pinfunction "2_2") (pintype "bidirectional"))
      (node (ref "C40") (pin "P$2") (pinfunction "2_P$2") (pintype "bidirectional"))
      (node (ref "C41") (pin "1") (pinfunction "1_1") (pintype "bidirectional"))
      (node (ref "C42") (pin "1") (pinfunction "1_1") (pintype "bidirectional"))
      (node (ref "C43") (pin "1") (pinfunction "1_1") (pintype "bidirectional"))
      (node (ref "C44") (pin "1") (pinfunction "1_1") (pintype "bidirectional"))
      (node (ref "C45") (pin "1") (pinfunction "1_1") (pintype "bidirectional"))
      (node (ref "C46") (pin "1") (pinfunction "1_1") (pintype "bidirectional"))
      (node (ref "C47") (pin "1") (pinfunction "1_1") (pintype "bidirectional"))
      (node (ref "C48") (pin "1") (pinfunction "1_1") (pintype "bidirectional"))
      (node (ref "C49") (pin "1") (pinfunction "1_1") (pintype "bidirectional"))
      (node (ref "C5") (pin "2") (pinfunction "2_2") (pintype "bidirectional"))
      (node (ref "C50") (pin "1") (pinfunction "1_1") (pintype "bidirectional"))
      (node (ref "C6") (pin "2") (pinfunction "2_2") (pintype "bidirectional"))
      (node (ref "C7") (pin "2") (pinfunction "2_2") (pintype "bidirectional"))
      (node (ref "C8") (pin "2") (pinfunction "2_2") (pintype "bidirectional"))
      (node (ref "C9") (pin "2") (pinfunction "2_2") (pintype "bidirectional"))
      (node (ref "D1") (pin "P$1") (pinfunction "ANODE_P$1") (pintype "bidirectional"))
      (node (ref "H1") (pin "B3,0") (pinfunction "MOUNT_B3,0") (pintype "passive"))
      (node (ref "H2") (pin "B3,0") (pinfunction "MOUNT_B3,0") (pintype "passive"))
      (node (ref "H3") (pin "B3,0") (pinfunction "MOUNT_B3,0") (pintype "passive"))
      (node (ref "H4") (pin "B3,0") (pinfunction "MOUNT_B3,0") (pintype "passive"))
      (node (ref "J1") (pin "1") (pinfunction "GND_1") (pintype "power_in"))
      (node (ref "J1") (pin "20") (pinfunction "VSOL-_20") (pintype "power_in"))
      (node (ref "J3") (pin "3") (pinfunction "GND_3") (pintype "bidirectional"))
      (node (ref "JP1") (pin "1") (pinfunction "1_1") (pintype "passive"))
      (node (ref "Q1") (pin "1") (pinfunction "S_1") (pintype "bidirectional"))
      (node (ref "R1") (pin "2") (pinfunction "2_2") (pintype "passive"))
      (node (ref "R14") (pin "1") (pinfunction "1_1") (pintype "passive"))
      (node (ref "R44") (pin "1") (pinfunction "1_1") (pintype "passive"))
      (node (ref "R50") (pin "1") (pinfunction "1_1") (pintype "passive"))
      (node (ref "R51") (pin "1") (pinfunction "1_1") (pintype "passive"))
      (node (ref "R52") (pin "1") (pinfunction "1_1") (pintype "passive"))
      (node (ref "R53") (pin "1") (pinfunction "1_1") (pintype "passive"))
      (node (ref "R56") (pin "1") (pinfunction "1_1") (pintype "passive"))
      (node (ref "R58") (pin "2") (pinfunction "2_2") (pintype "passive"))
      (node (ref "R71") (pin "1") (pinfunction "1_1") (pintype "passive"))
      (node (ref "RESET") (pin "3") (pinfunction "P$2_3") (pintype "passive"))
      (node (ref "RESET") (pin "4") (pinfunction "P$2_4") (pintype "passive"))
      (node (ref "S1") (pin "1") (pinfunction "A_1") (pintype "bidirectional"))
      (node (ref "U1") (pin "15") (pinfunction "PGND_15") (pintype "bidirectional"))
      (node (ref "U1") (pin "16") (pinfunction "PGND_16") (pintype "bidirectional"))
      (node (ref "U1") (pin "6") (pinfunction "AGND_6") (pintype "bidirectional"))
      (node (ref "U1") (pin "7") (pinfunction "FSW_7") (pintype "bidirectional"))
      (node (ref "U1") (pin "8") (pinfunction "DEF_8") (pintype "bidirectional"))
      (node (ref "U1") (pin "GND") (pinfunction "PGND_GND") (pintype "bidirectional"))
      (node (ref "U10") (pin "P$1") (pinfunction "GND_P$1") (pintype "open_collector"))
      (node (ref "U10") (pin "P2") (pinfunction "GND_P2") (pintype "open_collector"))
      (node (ref "U10") (pin "P3") (pinfunction "GND_P3") (pintype "open_collector"))
      (node (ref "U10") (pin "P7") (pinfunction "GND_P7") (pintype "open_collector"))
      (node (ref "U11") (pin "P$1") (pinfunction "GND_P$1") (pintype "open_collector"))
      (node (ref "U11") (pin "P2") (pinfunction "GND_P2") (pintype "open_collector"))
      (node (ref "U11") (pin "P3") (pinfunction "GND_P3") (pintype "open_collector"))
      (node (ref "U11") (pin "P7") (pinfunction "GND_P7") (pintype "open_collector"))
      (node (ref "U12") (pin "P$1") (pinfunction "GND_P$1") (pintype "open_collector"))
      (node (ref "U12") (pin "P2") (pinfunction "GND_P2") (pintype "open_collector"))
      (node (ref "U12") (pin "P3") (pinfunction "GND_P3") (pintype "open_collector"))
      (node (ref "U12") (pin "P7") (pinfunction "GND_P7") (pintype "open_collector"))
      (node (ref "U13") (pin "P$1") (pinfunction "GND_P$1") (pintype "open_collector"))
      (node (ref "U13") (pin "P2") (pinfunction "GND_P2") (pintype "open_collector"))
      (node (ref "U13") (pin "P3") (pinfunction "GND_P3") (pintype "open_collector"))
      (node (ref "U13") (pin "P7") (pinfunction "GND_P7") (pintype "open_collector"))
      (node (ref "U14") (pin "P$1") (pinfunction "GND_P$1") (pintype "open_collector"))
      (node (ref "U14") (pin "P2") (pinfunction "GND_P2") (pintype "open_collector"))
      (node (ref "U14") (pin "P3") (pinfunction "GND_P3") (pintype "open_collector"))
      (node (ref "U14") (pin "P7") (pinfunction "GND_P7") (pintype "open_collector"))
      (node (ref "U15") (pin "P$1") (pinfunction "GND_P$1") (pintype "open_collector"))
      (node (ref "U15") (pin "P2") (pinfunction "GND_P2") (pintype "open_collector"))
      (node (ref "U15") (pin "P3") (pinfunction "GND_P3") (pintype "open_collector"))
      (node (ref "U15") (pin "P7") (pinfunction "GND_P7") (pintype "open_collector"))
      (node (ref "U16") (pin "13") (pinfunction "GND_13") (pintype "bidirectional"))
      (node (ref "U16") (pin "6") (pinfunction "TIMER_6") (pintype "bidirectional"))
      (node (ref "U18") (pin "13") (pinfunction "CELLX_13") (pintype "bidirectional"))
      (node (ref "U18") (pin "15") (pinfunction "CSN_15") (pintype "bidirectional"))
      (node (ref "U18") (pin "4") (pinfunction "CSN_4") (pintype "bidirectional"))
      (node (ref "U18") (pin "6") (pinfunction "CELL2_6") (pintype "bidirectional"))
      (node (ref "U18") (pin "7") (pinfunction "CELL1_7") (pintype "bidirectional"))
      (node (ref "U19") (pin "P$1") (pinfunction "GND_P$1") (pintype "bidirectional"))
      (node (ref "U2") (pin "15") (pinfunction "PGND_15") (pintype "bidirectional"))
      (node (ref "U2") (pin "16") (pinfunction "PGND_16") (pintype "bidirectional"))
      (node (ref "U2") (pin "6") (pinfunction "AGND_6") (pintype "bidirectional"))
      (node (ref "U2") (pin "7") (pinfunction "FSW_7") (pintype "bidirectional"))
      (node (ref "U2") (pin "8") (pinfunction "DEF_8") (pintype "bidirectional"))
      (node (ref "U2") (pin "GND") (pinfunction "PGND_GND") (pintype "bidirectional"))
      (node (ref "U20") (pin "2") (pinfunction "GND_2") (pintype "bidirectional"))
      (node (ref "U21") (pin "2") (pinfunction "GND_2") (pintype "bidirectional"))
      (node (ref "U22") (pin "2") (pinfunction "GND_2") (pintype "bidirectional"))
      (node (ref "U23") (pin "2") (pinfunction "GND_2") (pintype "bidirectional"))
      (node (ref "U24") (pin "2") (pinfunction "GND_2") (pintype "bidirectional"))
      (node (ref "U25") (pin "1") (pinfunction "A0_1") (pintype "bidirectional"))
      (node (ref "U25") (pin "10") (pinfunction "GND_10") (pintype "bidirectional"))
      (node (ref "U25") (pin "3") (pinfunction "A2_3") (pintype "bidirectional"))
      (node (ref "U26") (pin "P$1") (pinfunction "GND_P$1") (pintype "open_collector"))
      (node (ref "U26") (pin "P2") (pinfunction "GND_P2") (pintype "open_collector"))
      (node (ref "U26") (pin "P3") (pinfunction "GND_P3") (pintype "open_collector"))
      (node (ref "U26") (pin "P7") (pinfunction "GND_P7") (pintype "open_collector"))
      (node (ref "U27") (pin "4") (pinfunction "GND_4") (pintype "bidirectional"))
      (node (ref "U28") (pin "3") (pinfunction "GND_3") (pintype "bidirectional"))
      (node (ref "U29") (pin "1") (pinfunction "E0_1") (pintype "bidirectional"))
      (node (ref "U29") (pin "2") (pinfunction "E1_2") (pintype "bidirectional"))
      (node (ref "U29") (pin "3") (pinfunction "E2_3") (pintype "bidirectional"))
      (node (ref "U29") (pin "4") (pinfunction "GND_4") (pintype "bidirectional"))
      (node (ref "U3") (pin "15") (pinfunction "PGND_15") (pintype "bidirectional"))
      (node (ref "U3") (pin "16") (pinfunction "PGND_16") (pintype "bidirectional"))
      (node (ref "U3") (pin "6") (pinfunction "AGND_6") (pintype "bidirectional"))
      (node (ref "U3") (pin "7") (pinfunction "FSW_7") (pintype "bidirectional"))
      (node (ref "U3") (pin "8") (pinfunction "DEF_8") (pintype "bidirectional"))
      (node (ref "U3") (pin "GND") (pinfunction "PGND_GND") (pintype "bidirectional"))
      (node (ref "U4") (pin "15") (pinfunction "PGND_15") (pintype "bidirectional"))
      (node (ref "U4") (pin "16") (pinfunction "PGND_16") (pintype "bidirectional"))
      (node (ref "U4") (pin "6") (pinfunction "AGND_6") (pintype "bidirectional"))
      (node (ref "U4") (pin "7") (pinfunction "FSW_7") (pintype "bidirectional"))
      (node (ref "U4") (pin "8") (pinfunction "DEF_8") (pintype "bidirectional"))
      (node (ref "U4") (pin "GND") (pinfunction "PGND_GND") (pintype "bidirectional"))
      (node (ref "U5") (pin "15") (pinfunction "PGND_15") (pintype "bidirectional"))
      (node (ref "U5") (pin "16") (pinfunction "PGND_16") (pintype "bidirectional"))
      (node (ref "U5") (pin "6") (pinfunction "AGND_6") (pintype "bidirectional"))
      (node (ref "U5") (pin "7") (pinfunction "FSW_7") (pintype "bidirectional"))
      (node (ref "U5") (pin "8") (pinfunction "DEF_8") (pintype "bidirectional"))
      (node (ref "U5") (pin "GND") (pinfunction "PGND_GND") (pintype "bidirectional"))
      (node (ref "U6") (pin "1") (pinfunction "A0_1") (pintype "bidirectional"))
      (node (ref "U6") (pin "10") (pinfunction "GND_10") (pintype "bidirectional"))
      (node (ref "U6") (pin "2") (pinfunction "A1_2") (pintype "bidirectional"))
      (node (ref "U6") (pin "3") (pinfunction "A2_3") (pintype "bidirectional"))
      (node (ref "U7") (pin "10") (pinfunction "GND_10") (pintype "bidirectional"))
      (node (ref "U7") (pin "2") (pinfunction "A1_2") (pintype "bidirectional"))
      (node (ref "U7") (pin "3") (pinfunction "A2_3") (pintype "bidirectional"))
      (node (ref "U8") (pin "2") (pinfunction "GND_2") (pintype "open_collector"))
      (node (ref "U9") (pin "P$1") (pinfunction "GND_P$1") (pintype "open_collector"))
      (node (ref "U9") (pin "P2") (pinfunction "GND_P2") (pintype "open_collector"))
      (node (ref "U9") (pin "P3") (pinfunction "GND_P3") (pintype "open_collector"))
      (node (ref "U9") (pin "P7") (pinfunction "GND_P7") (pintype "open_collector"))
    )
    (net (code "5") (name "Net-(D1-CATHODE)") (class "Default")
      (node (ref "C28") (pin "1") (pinfunction "1_1") (pintype "bidirectional"))
      (node (ref "D1") (pin "P$3") (pinfunction "CATHODE_P$3") (pintype "bidirectional"))
      (node (ref "L6") (pin "P$1") (pinfunction "1_P$1") (pintype "bidirectional"))
      (node (ref "U16") (pin "12") (pinfunction "SW_12") (pintype "bidirectional"))
    )
    (net (code "6") (name "Net-(D2-ANODE)") (class "Default")
      (node (ref "D2") (pin "P$2") (pinfunction "ANODE_P$2") (pintype "bidirectional"))
      (node (ref "D3") (pin "P$2") (pinfunction "ANODE_P$2") (pintype "bidirectional"))
    )
    (net (code "7") (name "Net-(D3-CATHODE)") (class "Default")
      (node (ref "C28") (pin "2") (pinfunction "2_2") (pintype "bidirectional"))
      (node (ref "D3") (pin "P$1") (pinfunction "CATHODE_P$1") (pintype "bidirectional"))
      (node (ref "U16") (pin "11") (pinfunction "BOOST_11") (pintype "bidirectional"))
    )
    (net (code "8") (name "Net-(L1-1)") (class "Default")
      (node (ref "L1") (pin "P$1") (pinfunction "1_P$1") (pintype "bidirectional"))
      (node (ref "U1") (pin "1") (pinfunction "SW_1") (pintype "bidirectional"))
      (node (ref "U1") (pin "2") (pinfunction "SW_2") (pintype "bidirectional"))
      (node (ref "U1") (pin "3") (pinfunction "SW_3") (pintype "bidirectional"))
    )
    (net (code "9") (name "Net-(L1-2)") (class "Default")
      (node (ref "C42") (pin "2") (pinfunction "2_2") (pintype "bidirectional"))
      (node (ref "L1") (pin "P$2") (pinfunction "2_P$2") (pintype "bidirectional"))
      (node (ref "R46") (pin "2") (pinfunction "2_2") (pintype "passive"))
      (node (ref "R59") (pin "2") (pinfunction "2_2") (pintype "passive"))
      (node (ref "U1") (pin "14") (pinfunction "VOS_14") (pintype "bidirectional"))
      (node (ref "U21") (pin "1") (pinfunction "IN_1") (pintype "bidirectional"))
      (node (ref "U21") (pin "3") (pinfunction "EN_3") (pintype "bidirectional"))
    )
    (net (code "10") (name "Net-(L2-1)") (class "Default")
      (node (ref "L2") (pin "P$1") (pinfunction "1_P$1") (pintype "bidirectional"))
      (node (ref "U2") (pin "1") (pinfunction "SW_1") (pintype "bidirectional"))
      (node (ref "U2") (pin "2") (pinfunction "SW_2") (pintype "bidirectional"))
      (node (ref "U2") (pin "3") (pinfunction "SW_3") (pintype "bidirectional"))
    )
    (net (code "11") (name "Net-(L2-2)") (class "Default")
      (node (ref "C43") (pin "2") (pinfunction "2_2") (pintype "bidirectional"))
      (node (ref "L2") (pin "P$2") (pinfunction "2_P$2") (pintype "bidirectional"))
      (node (ref "R47") (pin "2") (pinfunction "2_2") (pintype "passive"))
      (node (ref "R60") (pin "2") (pinfunction "2_2") (pintype "passive"))
      (node (ref "U2") (pin "14") (pinfunction "VOS_14") (pintype "bidirectional"))
      (node (ref "U22") (pin "1") (pinfunction "IN_1") (pintype "bidirectional"))
      (node (ref "U22") (pin "3") (pinfunction "EN_3") (pintype "bidirectional"))
    )
    (net (code "12") (name "Net-(L3-1)") (class "Default")
      (node (ref "L3") (pin "P$1") (pinfunction "1_P$1") (pintype "bidirectional"))
      (node (ref "U3") (pin "1") (pinfunction "SW_1") (pintype "bidirectional"))
      (node (ref "U3") (pin "2") (pinfunction "SW_2") (pintype "bidirectional"))
      (node (ref "U3") (pin "3") (pinfunction "SW_3") (pintype "bidirectional"))
    )
    (net (code "13") (name "Net-(L3-2)") (class "Default")
      (node (ref "C44") (pin "2") (pinfunction "2_2") (pintype "bidirectional"))
      (node (ref "L3") (pin "P$2") (pinfunction "2_P$2") (pintype "bidirectional"))
      (node (ref "R48") (pin "2") (pinfunction "2_2") (pintype "passive"))
      (node (ref "R61") (pin "2") (pinfunction "2_2") (pintype "passive"))
      (node (ref "U23") (pin "1") (pinfunction "IN_1") (pintype "bidirectional"))
      (node (ref "U23") (pin "3") (pinfunction "EN_3") (pintype "bidirectional"))
      (node (ref "U3") (pin "14") (pinfunction "VOS_14") (pintype "bidirectional"))
    )
    (net (code "14") (name "Net-(L4-1)") (class "Default")
      (node (ref "L4") (pin "P$1") (pinfunction "1_P$1") (pintype "bidirectional"))
      (node (ref "U4") (pin "1") (pinfunction "SW_1") (pintype "bidirectional"))
      (node (ref "U4") (pin "2") (pinfunction "SW_2") (pintype "bidirectional"))
      (node (ref "U4") (pin "3") (pinfunction "SW_3") (pintype "bidirectional"))
    )
    (net (code "15") (name "Net-(L4-2)") (class "Default")
      (node (ref "C41") (pin "2") (pinfunction "2_2") (pintype "bidirectional"))
      (node (ref "L4") (pin "P$2") (pinfunction "2_P$2") (pintype "bidirectional"))
      (node (ref "R45") (pin "2") (pinfunction "2_2") (pintype "passive"))
      (node (ref "R63") (pin "2") (pinfunction "2_2") (pintype "passive"))
      (node (ref "U20") (pin "1") (pinfunction "IN_1") (pintype "bidirectional"))
      (node (ref "U20") (pin "3") (pinfunction "EN_3") (pintype "bidirectional"))
      (node (ref "U4") (pin "14") (pinfunction "VOS_14") (pintype "bidirectional"))
    )
    (net (code "16") (name "Net-(L5-1)") (class "Default")
      (node (ref "L5") (pin "P$1") (pinfunction "1_P$1") (pintype "bidirectional"))
      (node (ref "U5") (pin "1") (pinfunction "SW_1") (pintype "bidirectional"))
      (node (ref "U5") (pin "2") (pinfunction "SW_2") (pintype "bidirectional"))
      (node (ref "U5") (pin "3") (pinfunction "SW_3") (pintype "bidirectional"))
    )
    (net (code "17") (name "Net-(L5-2)") (class "Default")
      (node (ref "C45") (pin "2") (pinfunction "2_2") (pintype "bidirectional"))
      (node (ref "L5") (pin "P$2") (pinfunction "2_P$2") (pintype "bidirectional"))
      (node (ref "R49") (pin "2") (pinfunction "2_2") (pintype "passive"))
      (node (ref "R62") (pin "2") (pinfunction "2_2") (pintype "passive"))
      (node (ref "U24") (pin "1") (pinfunction "IN_1") (pintype "bidirectional"))
      (node (ref "U24") (pin "3") (pinfunction "EN_3") (pintype "bidirectional"))
      (node (ref "U5") (pin "14") (pinfunction "VOS_14") (pintype "bidirectional"))
    )
    (net (code "18") (name "Net-(L6-2)") (class "Default")
      (node (ref "L6") (pin "P$2") (pinfunction "2_P$2") (pintype "bidirectional"))
      (node (ref "R10") (pin "1") (pinfunction "1_1") (pintype "passive"))
      (node (ref "U16") (pin "10") (pinfunction "SENSE_10") (pintype "bidirectional"))
    )
    (net (code "19") (name "Net-(Q1A-G)") (class "Default")
      (node (ref "Q1") (pin "2") (pinfunction "G_2") (pintype "bidirectional"))
      (node (ref "R14") (pin "2") (pinfunction "2_2") (pintype "passive"))
      (node (ref "R70") (pin "1") (pinfunction "1_1") (pintype "passive"))
      (node (ref "U27") (pin "7") (pinfunction "~{RESET}_7") (pintype "bidirectional"))
    )
    (net (code "20") (name "Net-(Q1B-G)") (class "Default")
      (node (ref "Q1") (pin "5") (pinfunction "G_5") (pintype "bidirectional"))
      (node (ref "R70") (pin "2") (pinfunction "2_2") (pintype "passive"))
    )
    (net (code "21") (name "Net-(Q1B-S)") (class "Default")
      (node (ref "Q1") (pin "4") (pinfunction "S_4") (pintype "bidirectional"))
      (node (ref "R71") (pin "2") (pinfunction "2_2") (pintype "passive"))
    )
    (net (code "22") (name "Net-(S1-B)") (class "Default")
      (node (ref "C26") (pin "1") (pinfunction "1_1") (pintype "bidirectional"))
      (node (ref "S1") (pin "2") (pinfunction "B_2") (pintype "bidirectional"))
    )
    (net (code "23") (name "Net-(U1-FB)") (class "Default")
      (node (ref "R50") (pin "2") (pinfunction "2_2") (pintype "passive"))
      (node (ref "R59") (pin "1") (pinfunction "1_1") (pintype "passive"))
      (node (ref "U1") (pin "5") (pinfunction "FB_5") (pintype "bidirectional"))
    )
    (net (code "24") (name "Net-(U1-PG)") (class "Default")
      (node (ref "R46") (pin "1") (pinfunction "1_1") (pintype "passive"))
      (node (ref "U1") (pin "4") (pinfunction "PG_4") (pintype "bidirectional"))
    )
    (net (code "25") (name "Net-(U1-SS{slash}TR)") (class "Default")
      (node (ref "C30") (pin "2") (pinfunction "2_2") (pintype "bidirectional"))
      (node (ref "U1") (pin "9") (pinfunction "SS/TR_9") (pintype "bidirectional"))
    )
    (net (code "26") (name "Net-(U2-FB)") (class "Default")
      (node (ref "R51") (pin "2") (pinfunction "2_2") (pintype "passive"))
      (node (ref "R60") (pin "1") (pinfunction "1_1") (pintype "passive"))
      (node (ref "U2") (pin "5") (pinfunction "FB_5") (pintype "bidirectional"))
    )
    (net (code "27") (name "Net-(U2-PG)") (class "Default")
      (node (ref "R47") (pin "1") (pinfunction "1_1") (pintype "passive"))
      (node (ref "U2") (pin "4") (pinfunction "PG_4") (pintype "bidirectional"))
    )
    (net (code "28") (name "Net-(U2-SS{slash}TR)") (class "Default")
      (node (ref "C31") (pin "2") (pinfunction "2_2") (pintype "bidirectional"))
      (node (ref "U2") (pin "9") (pinfunction "SS/TR_9") (pintype "bidirectional"))
    )
    (net (code "29") (name "Net-(U3-FB)") (class "Default")
      (node (ref "R52") (pin "2") (pinfunction "2_2") (pintype "passive"))
      (node (ref "R61") (pin "1") (pinfunction "1_1") (pintype "passive"))
      (node (ref "U3") (pin "5") (pinfunction "FB_5") (pintype "bidirectional"))
    )
    (net (code "30") (name "Net-(U3-PG)") (class "Default")
      (node (ref "R48") (pin "1") (pinfunction "1_1") (pintype "passive"))
      (node (ref "U3") (pin "4") (pinfunction "PG_4") (pintype "bidirectional"))
    )
    (net (code "31") (name "Net-(U3-SS{slash}TR)") (class "Default")
      (node (ref "C32") (pin "2") (pinfunction "2_2") (pintype "bidirectional"))
      (node (ref "U3") (pin "9") (pinfunction "SS/TR_9") (pintype "bidirectional"))
    )
    (net (code "32") (name "Net-(U4-FB)") (class "Default")
      (node (ref "R56") (pin "2") (pinfunction "2_2") (pintype "passive"))
      (node (ref "R63") (pin "1") (pinfunction "1_1") (pintype "passive"))
      (node (ref "U4") (pin "5") (pinfunction "FB_5") (pintype "bidirectional"))
    )
    (net (code "33") (name "Net-(U4-PG)") (class "Default")
      (node (ref "R45") (pin "1") (pinfunction "1_1") (pintype "passive"))
      (node (ref "U4") (pin "4") (pinfunction "PG_4") (pintype "bidirectional"))
    )
    (net (code "34") (name "Net-(U4-SS{slash}TR)") (class "Default")
      (node (ref "C29") (pin "2") (pinfunction "2_2") (pintype "bidirectional"))
      (node (ref "U4") (pin "9") (pinfunction "SS/TR_9") (pintype "bidirectional"))
    )
    (net (code "35") (name "Net-(U5-FB)") (class "Default")
      (node (ref "R53") (pin "2") (pinfunction "2_2") (pintype "passive"))
      (node (ref "R62") (pin "1") (pinfunction "1_1") (pintype "passive"))
      (node (ref "U5") (pin "5") (pinfunction "FB_5") (pintype "bidirectional"))
    )
    (net (code "36") (name "Net-(U5-PG)") (class "Default")
      (node (ref "R49") (pin "1") (pinfunction "1_1") (pintype "passive"))
      (node (ref "U5") (pin "4") (pinfunction "PG_4") (pintype "bidirectional"))
    )
    (net (code "37") (name "Net-(U5-SS{slash}TR)") (class "Default")
      (node (ref "C33") (pin "2") (pinfunction "2_2") (pintype "bidirectional"))
      (node (ref "U5") (pin "9") (pinfunction "SS/TR_9") (pintype "bidirectional"))
    )
    (net (code "38") (name "Net-(U6-SC0)") (class "Default")
      (node (ref "R18") (pin "1") (pinfunction "1_1") (pintype "passive"))
      (node (ref "U6") (pin "6") (pinfunction "SC0_6") (pintype "bidirectional"))
      (node (ref "U8") (pin "3") (pinfunction "SCL_3") (pintype "open_collector"))
    )
    (net (code "39") (name "Net-(U6-SC1)") (class "Default")
      (node (ref "R21") (pin "1") (pinfunction "1_1") (pintype "passive"))
      (node (ref "U6") (pin "9") (pinfunction "SC1_9") (pintype "bidirectional"))
      (node (ref "U9") (pin "P4") (pinfunction "SCL_P4") (pintype "open_collector"))
    )
    (net (code "40") (name "Net-(U6-SD0)") (class "Default")
      (node (ref "R17") (pin "1") (pinfunction "1_1") (pintype "passive"))
      (node (ref "U6") (pin "5") (pinfunction "SD0_5") (pintype "bidirectional"))
      (node (ref "U8") (pin "4") (pinfunction "SDA_4") (pintype "open_collector"))
    )
    (net (code "41") (name "Net-(U6-SD1)") (class "Default")
      (node (ref "R20") (pin "1") (pinfunction "1_1") (pintype "passive"))
      (node (ref "U6") (pin "8") (pinfunction "SD1_8") (pintype "bidirectional"))
      (node (ref "U9") (pin "P5") (pinfunction "SDA_P5") (pintype "open_collector"))
    )
    (net (code "42") (name "Net-(U6-~{INT0})") (class "Default")
      (node (ref "R19") (pin "1") (pinfunction "1_1") (pintype "passive"))
      (node (ref "U6") (pin "4") (pinfunction "~{INT0}_4") (pintype "bidirectional"))
      (node (ref "U8") (pin "5") (pinfunction "~{ALERT}_5") (pintype "open_collector"))
    )
    (net (code "43") (name "Net-(U6-~{INT1})") (class "Default")
      (node (ref "R22") (pin "1") (pinfunction "1_1") (pintype "passive"))
      (node (ref "U6") (pin "7") (pinfunction "~{INT1}_7") (pintype "bidirectional"))
      (node (ref "U9") (pin "P6") (pinfunction "~{ALERT}_P6") (pintype "open_collector"))
    )
    (net (code "44") (name "Net-(U10-SCL)") (class "Default")
      (node (ref "R24") (pin "1") (pinfunction "1_1") (pintype "passive"))
      (node (ref "U10") (pin "P4") (pinfunction "SCL_P4") (pintype "open_collector"))
      (node (ref "U6") (pin "13") (pinfunction "SC2_13") (pintype "bidirectional"))
    )
    (net (code "45") (name "Net-(U10-SDA)") (class "Default")
      (node (ref "R23") (pin "1") (pinfunction "1_1") (pintype "passive"))
      (node (ref "U10") (pin "P5") (pinfunction "SDA_P5") (pintype "open_collector"))
      (node (ref "U6") (pin "12") (pinfunction "SD2_12") (pintype "bidirectional"))
    )
    (net (code "46") (name "Net-(U10-~{ALERT})") (class "Default")
      (node (ref "R25") (pin "1") (pinfunction "1_1") (pintype "passive"))
      (node (ref "U10") (pin "P6") (pinfunction "~{ALERT}_P6") (pintype "open_collector"))
      (node (ref "U6") (pin "11") (pinfunction "~{INT2}_11") (pintype "bidirectional"))
    )
    (net (code "47") (name "Net-(U11-SCL)") (class "Default")
      (node (ref "R27") (pin "1") (pinfunction "1_1") (pintype "passive"))
      (node (ref "U11") (pin "P4") (pinfunction "SCL_P4") (pintype "open_collector"))
      (node (ref "U6") (pin "16") (pinfunction "SC3_16") (pintype "bidirectional"))
    )
    (net (code "48") (name "Net-(U11-SDA)") (class "Default")
      (node (ref "R26") (pin "1") (pinfunction "1_1") (pintype "passive"))
      (node (ref "U11") (pin "P5") (pinfunction "SDA_P5") (pintype "open_collector"))
      (node (ref "U6") (pin "15") (pinfunction "SD3_15") (pintype "bidirectional"))
    )
    (net (code "49") (name "Net-(U11-~{ALERT})") (class "Default")
      (node (ref "R28") (pin "1") (pinfunction "1_1") (pintype "passive"))
      (node (ref "U11") (pin "P6") (pinfunction "~{ALERT}_P6") (pintype "open_collector"))
      (node (ref "U6") (pin "14") (pinfunction "~{INT3}_14") (pintype "bidirectional"))
    )
    (net (code "50") (name "Net-(U12-SCL)") (class "Default")
      (node (ref "R36") (pin "1") (pinfunction "1_1") (pintype "passive"))
      (node (ref "U12") (pin "P4") (pinfunction "SCL_P4") (pintype "open_collector"))
      (node (ref "U7") (pin "6") (pinfunction "SC0_6") (pintype "bidirectional"))
    )
    (net (code "51") (name "Net-(U12-SDA)") (class "Default")
      (node (ref "R35") (pin "1") (pinfunction "1_1") (pintype "passive"))
      (node (ref "U12") (pin "P5") (pinfunction "SDA_P5") (pintype "open_collector"))
      (node (ref "U7") (pin "5") (pinfunction "SD0_5") (pintype "bidirectional"))
    )
    (net (code "52") (name "Net-(U12-~{ALERT})") (class "Default")
      (node (ref "R37") (pin "1") (pinfunction "1_1") (pintype "passive"))
      (node (ref "U12") (pin "P6") (pinfunction "~{ALERT}_P6") (pintype "open_collector"))
      (node (ref "U7") (pin "4") (pinfunction "~{INT0}_4") (pintype "bidirectional"))
    )
    (net (code "53") (name "Net-(U13-SCL)") (class "Default")
      (node (ref "R33") (pin "1") (pinfunction "1_1") (pintype "passive"))
      (node (ref "U13") (pin "P4") (pinfunction "SCL_P4") (pintype "open_collector"))
      (node (ref "U7") (pin "9") (pinfunction "SC1_9") (pintype "bidirectional"))
    )
    (net (code "54") (name "Net-(U13-SDA)") (class "Default")
      (node (ref "R32") (pin "1") (pinfunction "1_1") (pintype "passive"))
      (node (ref "U13") (pin "P5") (pinfunction "SDA_P5") (pintype "open_collector"))
      (node (ref "U7") (pin "8") (pinfunction "SD1_8") (pintype "bidirectional"))
    )
    (net (code "55") (name "Net-(U13-~{ALERT})") (class "Default")
      (node (ref "R34") (pin "1") (pinfunction "1_1") (pintype "passive"))
      (node (ref "U13") (pin "P6") (pinfunction "~{ALERT}_P6") (pintype "open_collector"))
      (node (ref "U7") (pin "7") (pinfunction "~{INT1}_7") (pintype "bidirectional"))
    )
    (net (code "56") (name "Net-(U14-SCL)") (class "Default")
      (node (ref "R30") (pin "1") (pinfunction "1_1") (pintype "passive"))
      (node (ref "U14") (pin "P4") (pinfunction "SCL_P4") (pintype "open_collector"))
      (node (ref "U7") (pin "13") (pinfunction "SC2_13") (pintype "bidirectional"))
    )
    (net (code "57") (name "Net-(U14-SDA)") (class "Default")
      (node (ref "R29") (pin "1") (pinfunction "1_1") (pintype "passive"))
      (node (ref "U14") (pin "P5") (pinfunction "SDA_P5") (pintype "open_collector"))
      (node (ref "U7") (pin "12") (pinfunction "SD2_12") (pintype "bidirectional"))
    )
    (net (code "58") (name "Net-(U14-~{ALERT})") (class "Default")
      (node (ref "R31") (pin "1") (pinfunction "1_1") (pintype "passive"))
      (node (ref "U14") (pin "P6") (pinfunction "~{ALERT}_P6") (pintype "open_collector"))
      (node (ref "U7") (pin "11") (pinfunction "~{INT2}_11") (pintype "bidirectional"))
    )
    (net (code "59") (name "Net-(U15-SCL)") (class "Default")
      (node (ref "R39") (pin "1") (pinfunction "1_1") (pintype "passive"))
      (node (ref "U15") (pin "P4") (pinfunction "SCL_P4") (pintype "open_collector"))
      (node (ref "U7") (pin "16") (pinfunction "SC3_16") (pintype "bidirectional"))
    )
    (net (code "60") (name "Net-(U15-SDA)") (class "Default")
      (node (ref "R38") (pin "1") (pinfunction "1_1") (pintype "passive"))
      (node (ref "U15") (pin "P5") (pinfunction "SDA_P5") (pintype "open_collector"))
      (node (ref "U7") (pin "15") (pinfunction "SD3_15") (pintype "bidirectional"))
    )
    (net (code "61") (name "Net-(U15-~{ALERT})") (class "Default")
      (node (ref "R40") (pin "1") (pinfunction "1_1") (pintype "passive"))
      (node (ref "U15") (pin "P6") (pinfunction "~{ALERT}_P6") (pintype "open_collector"))
      (node (ref "U7") (pin "14") (pinfunction "~{INT3}_14") (pintype "bidirectional"))
    )
    (net (code "62") (name "Net-(U16-VFB)") (class "Default")
      (node (ref "R58") (pin "1") (pinfunction "1_1") (pintype "passive"))
      (node (ref "R64") (pin "1") (pinfunction "1_1") (pintype "passive"))
      (node (ref "U16") (pin "7") (pinfunction "VFB_7") (pintype "bidirectional"))
    )
    (net (code "63") (name "Net-(U16-VIN_REG)") (class "Default")
      (node (ref "R12") (pin "1") (pinfunction "1_1") (pintype "passive"))
      (node (ref "R44") (pin "2") (pinfunction "2_2") (pintype "passive"))
      (node (ref "R57") (pin "1") (pinfunction "1_1") (pintype "passive"))
      (node (ref "U16") (pin "2") (pinfunction "VIN_REG_2") (pintype "bidirectional"))
      (node (ref "U17") (pin "6") (pinfunction "V-_6") (pintype "bidirectional"))
    )
    (net (code "64") (name "Net-(U17-R)") (class "Default")
      (node (ref "R12") (pin "2") (pinfunction "2_2") (pintype "passive"))
      (node (ref "U17") (pin "1") (pinfunction "R_1") (pintype "bidirectional"))
    )
    (net (code "65") (name "Net-(U18-ALRT1)") (class "Default")
      (node (ref "R13") (pin "1") (pinfunction "1_1") (pintype "passive"))
      (node (ref "U18") (pin "8") (pinfunction "ALRT1_8") (pintype "bidirectional"))
      (node (ref "U19") (pin "P$6") (pinfunction "VUSB_P$6") (pintype "bidirectional"))
    )
    (net (code "66") (name "Net-(U18-REG2)") (class "Default")
      (node (ref "C24") (pin "1") (pinfunction "1_1") (pintype "bidirectional"))
      (node (ref "U18") (pin "3") (pinfunction "REG2_3") (pintype "bidirectional"))
    )
    (net (code "67") (name "Net-(U18-REG3)") (class "Default")
      (node (ref "C25") (pin "1") (pinfunction "1_1") (pintype "bidirectional"))
      (node (ref "U18") (pin "1") (pinfunction "REG3_1") (pintype "bidirectional"))
    )
    (net (code "68") (name "Net-(U18-SCL)") (class "Default")
      (node (ref "R55") (pin "1") (pinfunction "1_1") (pintype "passive"))
      (node (ref "U18") (pin "11") (pinfunction "SCL_11") (pintype "bidirectional"))
      (node (ref "U19") (pin "P$5") (pinfunction "D+_P$5") (pintype "bidirectional"))
    )
    (net (code "69") (name "Net-(U18-SDA)") (class "Default")
      (node (ref "R54") (pin "1") (pinfunction "1_1") (pintype "passive"))
      (node (ref "U18") (pin "12") (pinfunction "SDA_12") (pintype "bidirectional"))
      (node (ref "U19") (pin "P$4") (pinfunction "D-_P$4") (pintype "bidirectional"))
    )
    (net (code "70") (name "Net-(U25-SC0)") (class "Default")
      (node (ref "R42") (pin "1") (pinfunction "1_1") (pintype "passive"))
      (node (ref "U25") (pin "6") (pinfunction "SC0_6") (pintype "bidirectional"))
      (node (ref "U26") (pin "P4") (pinfunction "SCL_P4") (pintype "open_collector"))
    )
    (net (code "71") (name "Net-(U25-SD0)") (class "Default")
      (node (ref "R41") (pin "1") (pinfunction "1_1") (pintype "passive"))
      (node (ref "U25") (pin "5") (pinfunction "SD0_5") (pintype "bidirectional"))
      (node (ref "U26") (pin "P5") (pinfunction "SDA_P5") (pintype "open_collector"))
    )
    (net (code "72") (name "Net-(U25-~{INT0})") (class "Default")
      (node (ref "R43") (pin "1") (pinfunction "1_1") (pintype "passive"))
      (node (ref "U25") (pin "4") (pinfunction "~{INT0}_4") (pintype "bidirectional"))
      (node (ref "U26") (pin "P6") (pinfunction "~{ALERT}_P6") (pintype "open_collector"))
    )
    (net (code "73") (name "Net-(U27-SRT)") (class "Default")
      (node (ref "C27") (pin "1") (pinfunction "1_1") (pintype "bidirectional"))
      (node (ref "U27") (pin "3") (pinfunction "SRT_3") (pintype "bidirectional"))
    )
    (net (code "74") (name "Net-(U27-SWT)") (class "Default")
      (node (ref "S1") (pin "IN") (pinfunction "IN_IN") (pintype "bidirectional"))
      (node (ref "U27") (pin "2") (pinfunction "SWT_2") (pintype "bidirectional"))
    )
    (net (code "75") (name "Net-(U27-VCC)") (class "Default")
      (node (ref "C22") (pin "1") (pinfunction "1_1") (pintype "bidirectional"))
      (node (ref "U27") (pin "5") (pinfunction "WDS_5") (pintype "bidirectional"))
      (node (ref "U27") (pin "8") (pinfunction "VCC_8") (pintype "bidirectional"))
      (node (ref "U28") (pin "1") (pinfunction "OUT_1") (pintype "bidirectional"))
    )
    (net (code "76") (name "Net-(U27-~{MR})") (class "Default")
      (node (ref "RESET") (pin "1") (pinfunction "P$1_1") (pintype "passive"))
      (node (ref "RESET") (pin "2") (pinfunction "P$1_2") (pintype "passive"))
      (node (ref "U27") (pin "1") (pinfunction "~{MR}_1") (pintype "bidirectional"))
    )
    (net (code "77") (name "Net-(U29-~{WC})") (class "Default")
      (node (ref "SJ1") (pin "2") (pinfunction "2_2") (pintype "passive"))
      (node (ref "U29") (pin "7") (pinfunction "~{WC}_7") (pintype "bidirectional"))
    )
    (net (code "78") (name "SCL") (class "Default")
      (node (ref "J1") (pin "5") (pinfunction "SMBCLK_5") (pintype "open_collector"))
      (node (ref "J3") (pin "1") (pinfunction "SCL_1") (pintype "bidirectional"))
      (node (ref "R55") (pin "2") (pinfunction "2_2") (pintype "passive"))
      (node (ref "U25") (pin "18") (pinfunction "SCL_18") (pintype "bidirectional"))
      (node (ref "U29") (pin "6") (pinfunction "SCL_6") (pintype "bidirectional"))
      (node (ref "U6") (pin "18") (pinfunction "SCL_18") (pintype "bidirectional"))
      (node (ref "U7") (pin "18") (pinfunction "SCL_18") (pintype "bidirectional"))
    )
    (net (code "79") (name "SDA") (class "Default")
      (node (ref "J1") (pin "3") (pinfunction "SMBDATA_3") (pintype "open_collector"))
      (node (ref "J3") (pin "5") (pinfunction "SDA_5") (pintype "bidirectional"))
      (node (ref "R54") (pin "2") (pinfunction "2_2") (pintype "passive"))
      (node (ref "U25") (pin "19") (pinfunction "SDA_19") (pintype "bidirectional"))
      (node (ref "U29") (pin "5") (pinfunction "SDA_5") (pintype "bidirectional"))
      (node (ref "U6") (pin "19") (pinfunction "SDA_19") (pintype "bidirectional"))
      (node (ref "U7") (pin "19") (pinfunction "SDA_19") (pintype "bidirectional"))
    )
    (net (code "80") (name "VBAT+") (class "Default")
      (node (ref "C10") (pin "1") (pinfunction "1_1") (pintype "bidirectional"))
      (node (ref "C11") (pin "1") (pinfunction "1_1") (pintype "bidirectional"))
      (node (ref "C12") (pin "1") (pinfunction "1_1") (pintype "bidirectional"))
      (node (ref "C13") (pin "1") (pinfunction "1_1") (pintype "bidirectional"))
      (node (ref "C14") (pin "1") (pinfunction "1_1") (pintype "bidirectional"))
      (node (ref "C21") (pin "1") (pinfunction "1_1") (pintype "bidirectional"))
      (node (ref "C34") (pin "P$1") (pinfunction "1_P$1") (pintype "bidirectional"))
      (node (ref "C35") (pin "P$1") (pinfunction "1_P$1") (pintype "bidirectional"))
      (node (ref "C36") (pin "P$1") (pinfunction "1_P$1") (pintype "bidirectional"))
      (node (ref "C37") (pin "P$1") (pinfunction "1_P$1") (pintype "bidirectional"))
      (node (ref "C38") (pin "P$1") (pinfunction "1_P$1") (pintype "bidirectional"))
      (node (ref "C39") (pin "P$1") (pinfunction "1_P$1") (pintype "bidirectional"))
      (node (ref "C9") (pin "1") (pinfunction "1_1") (pintype "bidirectional"))
      (node (ref "D2") (pin "P$1") (pinfunction "CATHODE_P$1") (pintype "bidirectional"))
      (node (ref "J1") (pin "17") (pinfunction "VBATT+_17") (pintype "power_in"))
      (node (ref "JP1") (pin "4") (pinfunction "4_4") (pintype "passive"))
      (node (ref "R10") (pin "2") (pinfunction "2_2") (pintype "passive"))
      (node (ref "R64") (pin "2") (pinfunction "2_2") (pintype "passive"))
      (node (ref "R65") (pin "1") (pinfunction "1_1") (pintype "passive"))
      (node (ref "U1") (pin "10") (pinfunction "AVIN_10") (pintype "bidirectional"))
      (node (ref "U1") (pin "11") (pinfunction "PVIN_11") (pintype "bidirectional"))
      (node (ref "U1") (pin "12") (pinfunction "PVIN_12") (pintype "bidirectional"))
      (node (ref "U16") (pin "9") (pinfunction "BAT_9") (pintype "bidirectional"))
      (node (ref "U18") (pin "5") (pinfunction "VBATT_5") (pintype "bidirectional"))
      (node (ref "U2") (pin "10") (pinfunction "AVIN_10") (pintype "bidirectional"))
      (node (ref "U2") (pin "11") (pinfunction "PVIN_11") (pintype "bidirectional"))
      (node (ref "U2") (pin "12") (pinfunction "PVIN_12") (pintype "bidirectional"))
      (node (ref "U28") (pin "2") (pinfunction "IN_2") (pintype "bidirectional"))
      (node (ref "U3") (pin "10") (pinfunction "AVIN_10") (pintype "bidirectional"))
      (node (ref "U3") (pin "11") (pinfunction "PVIN_11") (pintype "bidirectional"))
      (node (ref "U3") (pin "12") (pinfunction "PVIN_12") (pintype "bidirectional"))
      (node (ref "U4") (pin "10") (pinfunction "AVIN_10") (pintype "bidirectional"))
      (node (ref "U4") (pin "11") (pinfunction "PVIN_11") (pintype "bidirectional"))
      (node (ref "U4") (pin "12") (pinfunction "PVIN_12") (pintype "bidirectional"))
      (node (ref "U5") (pin "10") (pinfunction "AVIN_10") (pintype "bidirectional"))
      (node (ref "U5") (pin "11") (pinfunction "PVIN_11") (pintype "bidirectional"))
      (node (ref "U5") (pin "12") (pinfunction "PVIN_12") (pintype "bidirectional"))
    )
    (net (code "81") (name "VBAT-") (class "Default")
      (node (ref "J1") (pin "18") (pinfunction "VBATT-_18") (pintype "power_in"))
      (node (ref "JP1") (pin "3") (pinfunction "3_3") (pintype "passive"))
      (node (ref "R1") (pin "1") (pinfunction "1_1") (pintype "passive"))
      (node (ref "U18") (pin "2") (pinfunction "CSP_2") (pintype "bidirectional"))
    )
    (net (code "82") (name "VCC_3V3") (class "Default")
      (node (ref "3V3") (pin "TESTPOINT") (pinfunction "TESTPOINT_TESTPOINT") (pintype "bidirectional"))
      (node (ref "C15") (pin "1") (pinfunction "1_1") (pintype "bidirectional"))
      (node (ref "C46") (pin "2") (pinfunction "2_2") (pintype "bidirectional"))
      (node (ref "R17") (pin "2") (pinfunction "2_2") (pintype "passive"))
      (node (ref "R18") (pin "2") (pinfunction "2_2") (pintype "passive"))
      (node (ref "R19") (pin "2") (pinfunction "2_2") (pintype "passive"))
      (node (ref "R2") (pin "2") (pinfunction "2_2") (pintype "passive"))
      (node (ref "U20") (pin "5") (pinfunction "OUT_5") (pintype "bidirectional"))
      (node (ref "U8") (pin "1") (pinfunction "SENSE+_1") (pintype "open_collector"))
    )
    (net (code "83") (name "VCC_5V_1") (class "Default")
      (node (ref "5V_1") (pin "TESTPOINT") (pinfunction "TESTPOINT_TESTPOINT") (pintype "bidirectional"))
      (node (ref "C16") (pin "1") (pinfunction "1_1") (pintype "bidirectional"))
      (node (ref "C47") (pin "2") (pinfunction "2_2") (pintype "bidirectional"))
      (node (ref "R20") (pin "2") (pinfunction "2_2") (pintype "passive"))
      (node (ref "R21") (pin "2") (pinfunction "2_2") (pintype "passive"))
      (node (ref "R22") (pin "2") (pinfunction "2_2") (pintype "passive"))
      (node (ref "R3") (pin "2") (pinfunction "2_2") (pintype "passive"))
      (node (ref "U21") (pin "5") (pinfunction "OUT_5") (pintype "bidirectional"))
      (node (ref "U9") (pin "P1") (pinfunction "SENSE+_P1") (pintype "open_collector"))
    )
    (net (code "84") (name "VCC_5V_2") (class "Default")
      (node (ref "5V_2") (pin "TESTPOINT") (pinfunction "TESTPOINT_TESTPOINT") (pintype "bidirectional"))
      (node (ref "C17") (pin "1") (pinfunction "1_1") (pintype "bidirectional"))
      (node (ref "C48") (pin "2") (pinfunction "2_2") (pintype "bidirectional"))
      (node (ref "R23") (pin "2") (pinfunction "2_2") (pintype "passive"))
      (node (ref "R24") (pin "2") (pinfunction "2_2") (pintype "passive"))
      (node (ref "R25") (pin "2") (pinfunction "2_2") (pintype "passive"))
      (node (ref "R26") (pin "2") (pinfunction "2_2") (pintype "passive"))
      (node (ref "R27") (pin "2") (pinfunction "2_2") (pintype "passive"))
      (node (ref "R28") (pin "2") (pinfunction "2_2") (pintype "passive"))
      (node (ref "R4") (pin "2") (pinfunction "2_2") (pintype "passive"))
      (node (ref "R5") (pin "2") (pinfunction "2_2") (pintype "passive"))
      (node (ref "U10") (pin "P1") (pinfunction "SENSE+_P1") (pintype "open_collector"))
      (node (ref "U11") (pin "P1") (pinfunction "SENSE+_P1") (pintype "open_collector"))
      (node (ref "U22") (pin "5") (pinfunction "OUT_5") (pintype "bidirectional"))
    )
    (net (code "85") (name "VCC_5V_3") (class "Default")
      (node (ref "5V_3") (pin "TESTPOINT") (pinfunction "TESTPOINT_TESTPOINT") (pintype "bidirectional"))
      (node (ref "C18") (pin "1") (pinfunction "1_1") (pintype "bidirectional"))
      (node (ref "C49") (pin "2") (pinfunction "2_2") (pintype "bidirectional"))
      (node (ref "R32") (pin "2") (pinfunction "2_2") (pintype "passive"))
      (node (ref "R33") (pin "2") (pinfunction "2_2") (pintype "passive"))
      (node (ref "R34") (pin "2") (pinfunction "2_2") (pintype "passive"))
      (node (ref "R35") (pin "2") (pinfunction "2_2") (pintype "passive"))
      (node (ref "R36") (pin "2") (pinfunction "2_2") (pintype "passive"))
      (node (ref "R37") (pin "2") (pinfunction "2_2") (pintype "passive"))
      (node (ref "R6") (pin "2") (pinfunction "2_2") (pintype "passive"))
      (node (ref "R7") (pin "2") (pinfunction "2_2") (pintype "passive"))
      (node (ref "U12") (pin "P1") (pinfunction "SENSE+_P1") (pintype "open_collector"))
      (node (ref "U13") (pin "P1") (pinfunction "SENSE+_P1") (pintype "open_collector"))
      (node (ref "U23") (pin "5") (pinfunction "OUT_5") (pintype "bidirectional"))
    )
    (net (code "86") (name "VCC_5V_4") (class "Default")
      (node (ref "5V_4") (pin "TESTPOINT") (pinfunction "TESTPOINT_TESTPOINT") (pintype "bidirectional"))
      (node (ref "C19") (pin "1") (pinfunction "1_1") (pintype "bidirectional"))
      (node (ref "C50") (pin "2") (pinfunction "2_2") (pintype "bidirectional"))
      (node (ref "R29") (pin "2") (pinfunction "2_2") (pintype "passive"))
      (node (ref "R30") (pin "2") (pinfunction "2_2") (pintype "passive"))
      (node (ref "R31") (pin "2") (pinfunction "2_2") (pintype "passive"))
      (node (ref "R38") (pin "2") (pinfunction "2_2") (pintype "passive"))
      (node (ref "R39") (pin "2") (pinfunction "2_2") (pintype "passive"))
      (node (ref "R40") (pin "2") (pinfunction "2_2") (pintype "passive"))
      (node (ref "R8") (pin "2") (pinfunction "2_2") (pintype "passive"))
      (node (ref "R9") (pin "2") (pinfunction "2_2") (pintype "passive"))
      (node (ref "U14") (pin "P1") (pinfunction "SENSE+_P1") (pintype "open_collector"))
      (node (ref "U15") (pin "P1") (pinfunction "SENSE+_P1") (pintype "open_collector"))
      (node (ref "U24") (pin "5") (pinfunction "OUT_5") (pintype "bidirectional"))
    )
    (net (code "87") (name "VCC_BACKPLANE") (class "Default")
      (node (ref "C1") (pin "1") (pinfunction "1_1") (pintype "bidirectional"))
      (node (ref "C23") (pin "1") (pinfunction "1_1") (pintype "bidirectional"))
      (node (ref "J1") (pin "13") (pinfunction "VCC_BACKPLANE_13") (pintype "power_in"))
      (node (ref "J1") (pin "2") (pinfunction "VCC_CONTROLLER_2") (pintype "power_in"))
      (node (ref "J3") (pin "6") (pinfunction "VCC_6") (pintype "bidirectional"))
      (node (ref "Q1") (pin "3") (pinfunction "D_3") (pintype "bidirectional"))
      (node (ref "R15") (pin "2") (pinfunction "2_2") (pintype "passive"))
      (node (ref "R16") (pin "2") (pinfunction "2_2") (pintype "passive"))
      (node (ref "R2") (pin "1") (pinfunction "1_1") (pintype "passive"))
      (node (ref "R41") (pin "2") (pinfunction "2_2") (pintype "passive"))
      (node (ref "R42") (pin "2") (pinfunction "2_2") (pintype "passive"))
      (node (ref "R43") (pin "2") (pinfunction "2_2") (pintype "passive"))
      (node (ref "SJ1") (pin "1") (pinfunction "1_1") (pintype "passive"))
      (node (ref "U25") (pin "2") (pinfunction "A1_2") (pintype "bidirectional"))
      (node (ref "U25") (pin "20") (pinfunction "VCC_20") (pintype "bidirectional"))
      (node (ref "U29") (pin "8") (pinfunction "VCC_8") (pintype "bidirectional"))
      (node (ref "U6") (pin "20") (pinfunction "VCC_20") (pintype "bidirectional"))
      (node (ref "U7") (pin "1") (pinfunction "A0_1") (pintype "bidirectional"))
      (node (ref "U7") (pin "20") (pinfunction "VCC_20") (pintype "bidirectional"))
      (node (ref "U8") (pin "6") (pinfunction "SENSE-_6") (pintype "open_collector"))
    )
    (net (code "88") (name "VCC_LINUX") (class "Default")
      (node (ref "C2") (pin "1") (pinfunction "1_1") (pintype "bidirectional"))
      (node (ref "J1") (pin "4") (pinfunction "VCC_LINUX_4") (pintype "power_in"))
      (node (ref "R3") (pin "1") (pinfunction "1_1") (pintype "passive"))
      (node (ref "U9") (pin "P8") (pinfunction "SENSE-_P8") (pintype "open_collector"))
    )
    (net (code "89") (name "VCC_MOD0") (class "Default")
      (node (ref "C3") (pin "1") (pinfunction "1_1") (pintype "bidirectional"))
      (node (ref "J1") (pin "7") (pinfunction "VCC_MOD0_7") (pintype "power_in"))
      (node (ref "R4") (pin "1") (pinfunction "1_1") (pintype "passive"))
      (node (ref "U10") (pin "P8") (pinfunction "SENSE-_P8") (pintype "open_collector"))
    )
    (net (code "90") (name "VCC_MOD1") (class "Default")
      (node (ref "C4") (pin "1") (pinfunction "1_1") (pintype "bidirectional"))
      (node (ref "J1") (pin "8") (pinfunction "VCC_MOD1_8") (pintype "power_in"))
      (node (ref "R5") (pin "1") (pinfunction "1_1") (pintype "passive"))
      (node (ref "U11") (pin "P8") (pinfunction "SENSE-_P8") (pintype "open_collector"))
    )
    (net (code "91") (name "VCC_MOD2") (class "Default")
      (node (ref "C5") (pin "1") (pinfunction "1_1") (pintype "bidirectional"))
      (node (ref "J1") (pin "9") (pinfunction "VCC_MOD2_9") (pintype "power_in"))
      (node (ref "R6") (pin "1") (pinfunction "1_1") (pintype "passive"))
      (node (ref "U12") (pin "P8") (pinfunction "SENSE-_P8") (pintype "open_collector"))
    )
    (net (code "92") (name "VCC_MOD5") (class "Default")
      (node (ref "C6") (pin "1") (pinfunction "1_1") (pintype "bidirectional"))
      (node (ref "J1") (pin "10") (pinfunction "VCC_MOD5_10") (pintype "power_in"))
      (node (ref "R7") (pin "1") (pinfunction "1_1") (pintype "passive"))
      (node (ref "U13") (pin "P8") (pinfunction "SENSE-_P8") (pintype "open_collector"))
    )
    (net (code "93") (name "VCC_MOD6") (class "Default")
      (node (ref "C7") (pin "1") (pinfunction "1_1") (pintype "bidirectional"))
      (node (ref "J1") (pin "11") (pinfunction "VCC_MOD6_11") (pintype "power_in"))
      (node (ref "R8") (pin "1") (pinfunction "1_1") (pintype "passive"))
      (node (ref "U14") (pin "P8") (pinfunction "SENSE-_P8") (pintype "open_collector"))
    )
    (net (code "94") (name "VCC_MOD7") (class "Default")
      (node (ref "C8") (pin "1") (pinfunction "1_1") (pintype "bidirectional"))
      (node (ref "J1") (pin "12") (pinfunction "VCC_MOD7_12") (pintype "power_in"))
      (node (ref "R9") (pin "1") (pinfunction "1_1") (pintype "passive"))
      (node (ref "U15") (pin "P8") (pinfunction "SENSE-_P8") (pintype "open_collector"))
    )
    (net (code "95") (name "VSOL+") (class "Default")
      (node (ref "C20") (pin "1") (pinfunction "1_1") (pintype "bidirectional"))
      (node (ref "J1") (pin "19") (pinfunction "VSOL+_19") (pintype "power_in"))
      (node (ref "JP1") (pin "2") (pinfunction "2_2") (pintype "passive"))
      (node (ref "R11") (pin "2") (pinfunction "2_2") (pintype "passive"))
      (node (ref "U26") (pin "P1") (pinfunction "SENSE+_P1") (pintype "open_collector"))
    )
    (net (code "96") (name "VSOL_SENSE") (class "Default")
      (node (ref "C40") (pin "P$1") (pinfunction "1_P$1") (pintype "bidirectional"))
      (node (ref "R11") (pin "1") (pinfunction "1_1") (pintype "passive"))
      (node (ref "R57") (pin "2") (pinfunction "2_2") (pintype "passive"))
      (node (ref "U16") (pin "1") (pinfunction "VIN_1") (pintype "bidirectional"))
      (node (ref "U16") (pin "3") (pinfunction "~{SHDN}_3") (pintype "bidirectional"))
      (node (ref "U17") (pin "4") (pinfunction "V+_4") (pintype "bidirectional"))
      (node (ref "U26") (pin "P8") (pinfunction "SENSE-_P8") (pintype "open_collector"))
    )
    (net (code "97") (name "WDI") (class "Default")
      (node (ref "J1") (pin "16") (pinfunction "WDI_16") (pintype "power_in"))
      (node (ref "U27") (pin "6") (pinfunction "WDI_6") (pintype "bidirectional"))
    )
    (net (code "98") (name "unconnected-(U16-NTC-Pad8)") (class "Default")
      (node (ref "U16") (pin "8") (pinfunction "NTC_8") (pintype "bidirectional"))
    )
    (net (code "99") (name "unconnected-(U18-AIN1-Pad9)") (class "Default")
      (node (ref "U18") (pin "9") (pinfunction "AIN1_9") (pintype "bidirectional"))
    )
    (net (code "100") (name "unconnected-(U18-AIN2-Pad10)") (class "Default")
      (node (ref "U18") (pin "10") (pinfunction "AIN2_10") (pintype "bidirectional"))
    )
    (net (code "101") (name "unconnected-(U18-THRM-Pad14)") (class "Default")
      (node (ref "U18") (pin "14") (pinfunction "THRM_14") (pintype "bidirectional"))
    )
    (net (code "102") (name "unconnected-(U20-FLG-Pad4)") (class "Default")
      (node (ref "U20") (pin "4") (pinfunction "FLG_4") (pintype "bidirectional"))
    )
    (net (code "103") (name "unconnected-(U21-FLG-Pad4)") (class "Default")
      (node (ref "U21") (pin "4") (pinfunction "FLG_4") (pintype "bidirectional"))
    )
    (net (code "104") (name "unconnected-(U22-FLG-Pad4)") (class "Default")
      (node (ref "U22") (pin "4") (pinfunction "FLG_4") (pintype "bidirectional"))
    )
    (net (code "105") (name "unconnected-(U23-FLG-Pad4)") (class "Default")
      (node (ref "U23") (pin "4") (pinfunction "FLG_4") (pintype "bidirectional"))
    )
    (net (code "106") (name "unconnected-(U24-FLG-Pad4)") (class "Default")
      (node (ref "U24") (pin "4") (pinfunction "FLG_4") (pintype "bidirectional"))
    )
    (net (code "107") (name "unconnected-(U25-SC1-Pad9)") (class "Default")
      (node (ref "U25") (pin "9") (pinfunction "SC1_9") (pintype "bidirectional"))
    )
    (net (code "108") (name "unconnected-(U25-SC2-Pad13)") (class "Default")
      (node (ref "U25") (pin "13") (pinfunction "SC2_13") (pintype "bidirectional"))
    )
    (net (code "109") (name "unconnected-(U25-SC3-Pad16)") (class "Default")
      (node (ref "U25") (pin "16") (pinfunction "SC3_16") (pintype "bidirectional"))
    )
    (net (code "110") (name "unconnected-(U25-SD1-Pad8)") (class "Default")
      (node (ref "U25") (pin "8") (pinfunction "SD1_8") (pintype "bidirectional"))
    )
    (net (code "111") (name "unconnected-(U25-SD2-Pad12)") (class "Default")
      (node (ref "U25") (pin "12") (pinfunction "SD2_12") (pintype "bidirectional"))
    )
    (net (code "112") (name "unconnected-(U25-SD3-Pad15)") (class "Default")
      (node (ref "U25") (pin "15") (pinfunction "SD3_15") (pintype "bidirectional"))
    )
    (net (code "113") (name "unconnected-(U25-~{INT1}-Pad7)") (class "Default")
      (node (ref "U25") (pin "7") (pinfunction "~{INT1}_7") (pintype "bidirectional"))
    )
    (net (code "114") (name "unconnected-(U25-~{INT2}-Pad11)") (class "Default")
      (node (ref "U25") (pin "11") (pinfunction "~{INT2}_11") (pintype "bidirectional"))
    )
    (net (code "115") (name "unconnected-(U25-~{INT3}-Pad14)") (class "Default")
      (node (ref "U25") (pin "14") (pinfunction "~{INT3}_14") (pintype "bidirectional"))
    )
    (net (code "116") (name "~{INT}") (class "Default")
      (node (ref "J1") (pin "6") (pinfunction "~{SMBALERT}_6") (pintype "bidirectional"))
      (node (ref "R13") (pin "2") (pinfunction "2_2") (pintype "passive"))
      (node (ref "U25") (pin "17") (pinfunction "~{INT}_17") (pintype "bidirectional"))
      (node (ref "U6") (pin "17") (pinfunction "~{INT}_17") (pintype "bidirectional"))
      (node (ref "U7") (pin "17") (pinfunction "~{INT}_17") (pintype "bidirectional"))
    )
  )
)
